# CP80_Preamp.net
KiCad netlist of a schematic drawn in Altium Designer
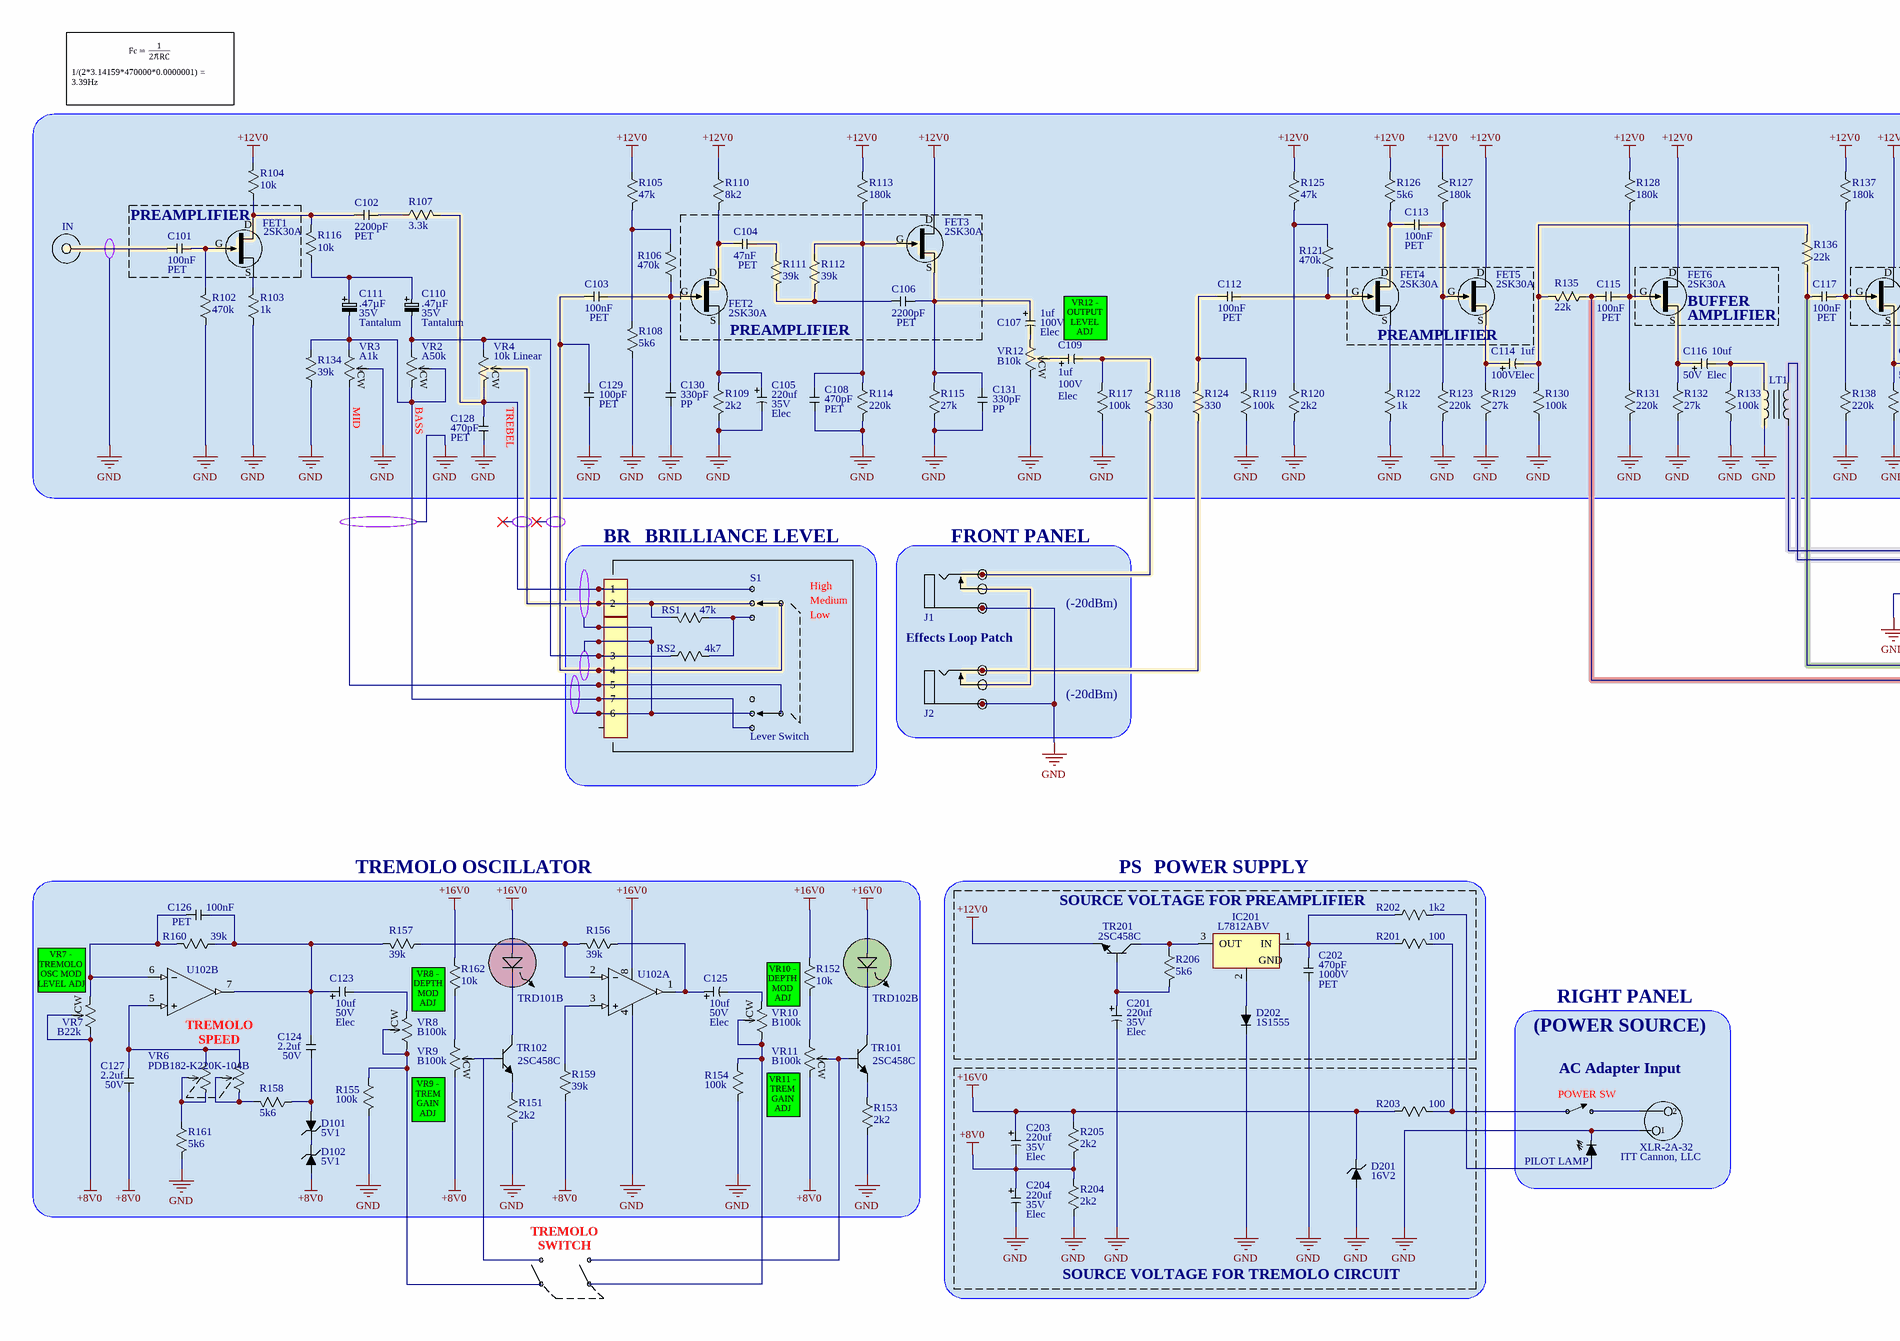
[diagram p0: CP80 Preamp.SchDoc, top left]
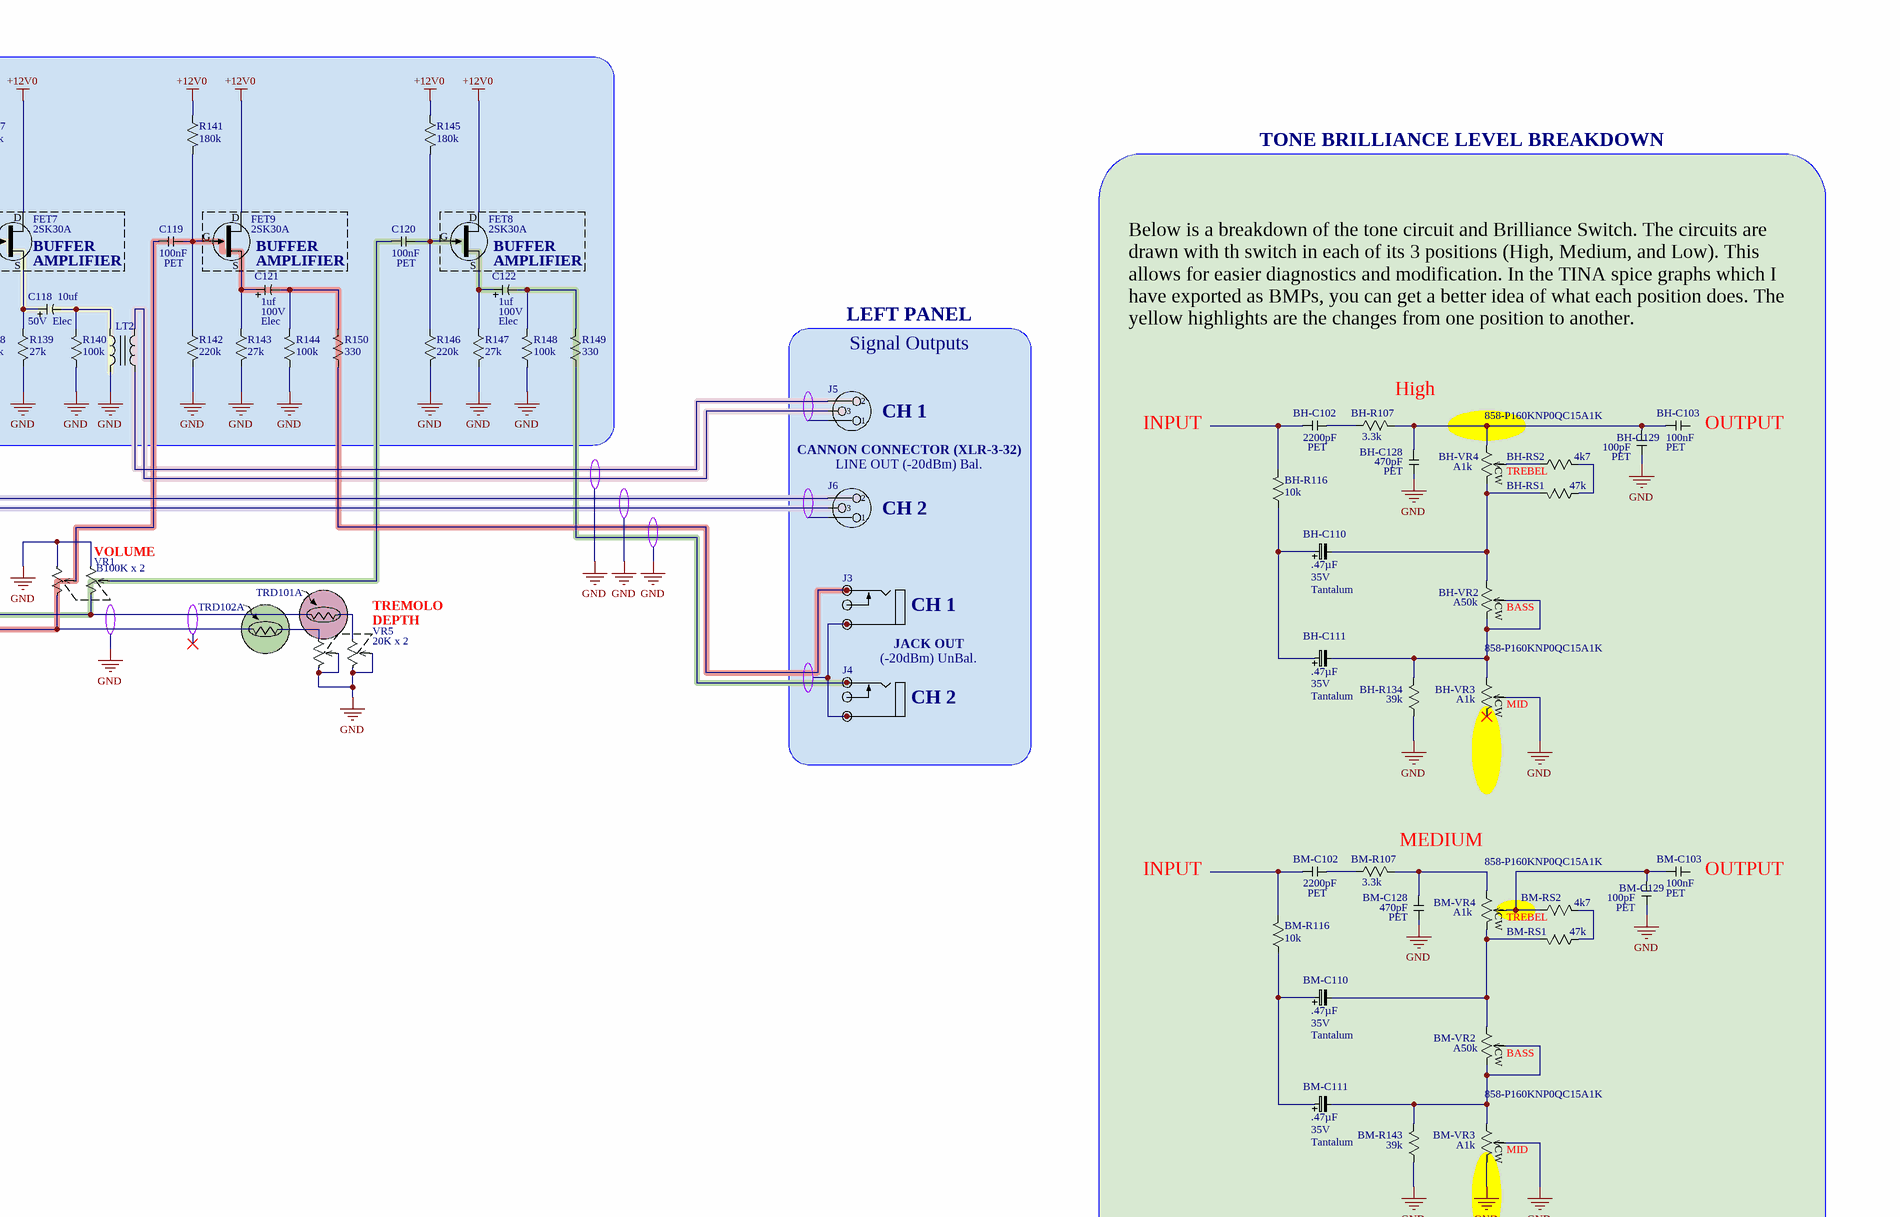
[diagram p1: CP80 Preamp.SchDoc, top right]
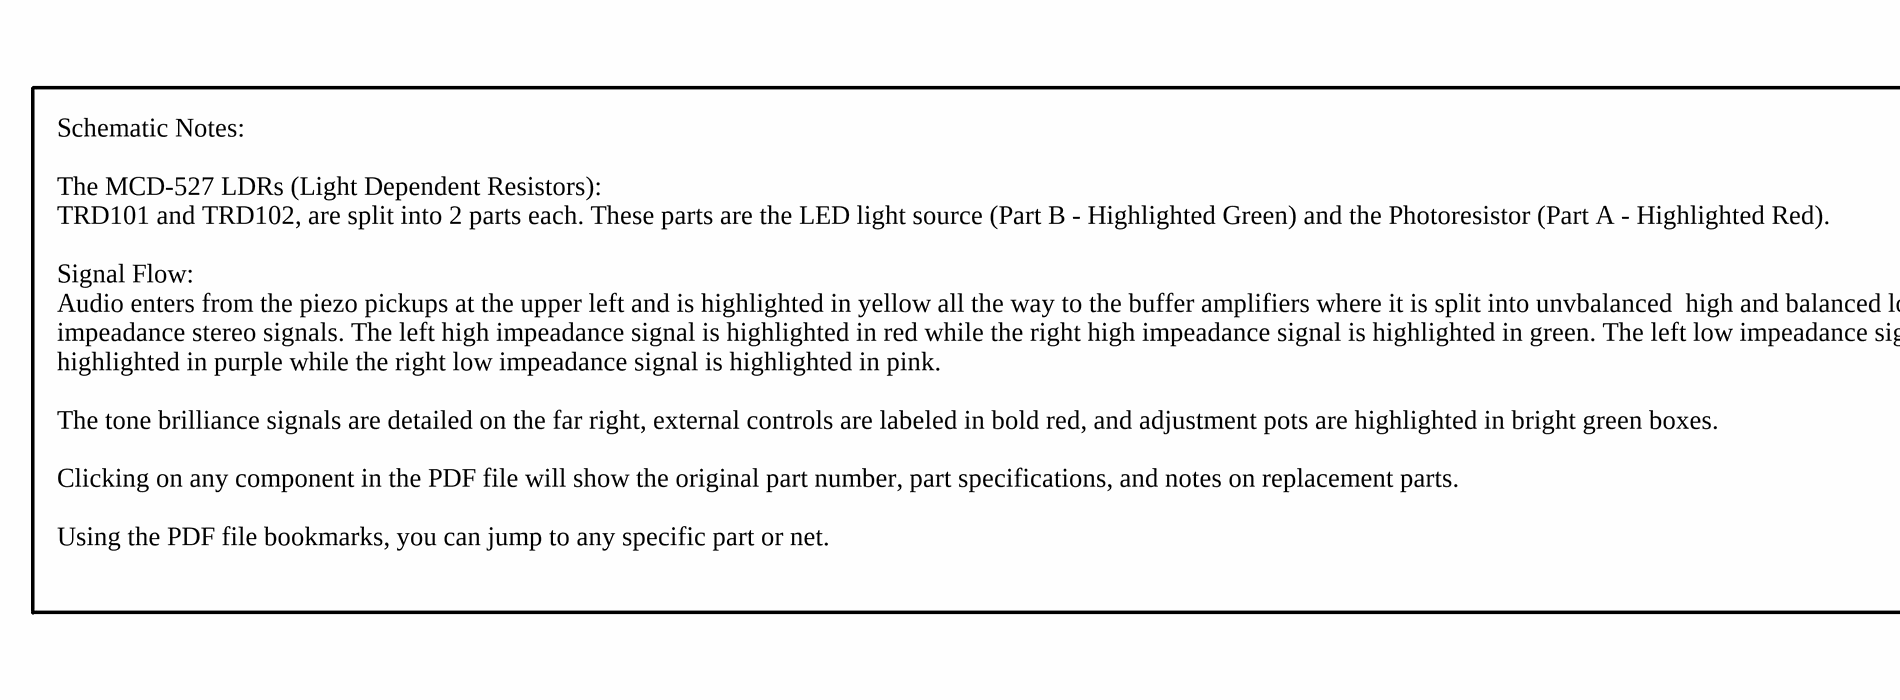
[diagram p2: CP80 Preamp.SchDoc, bottom left]
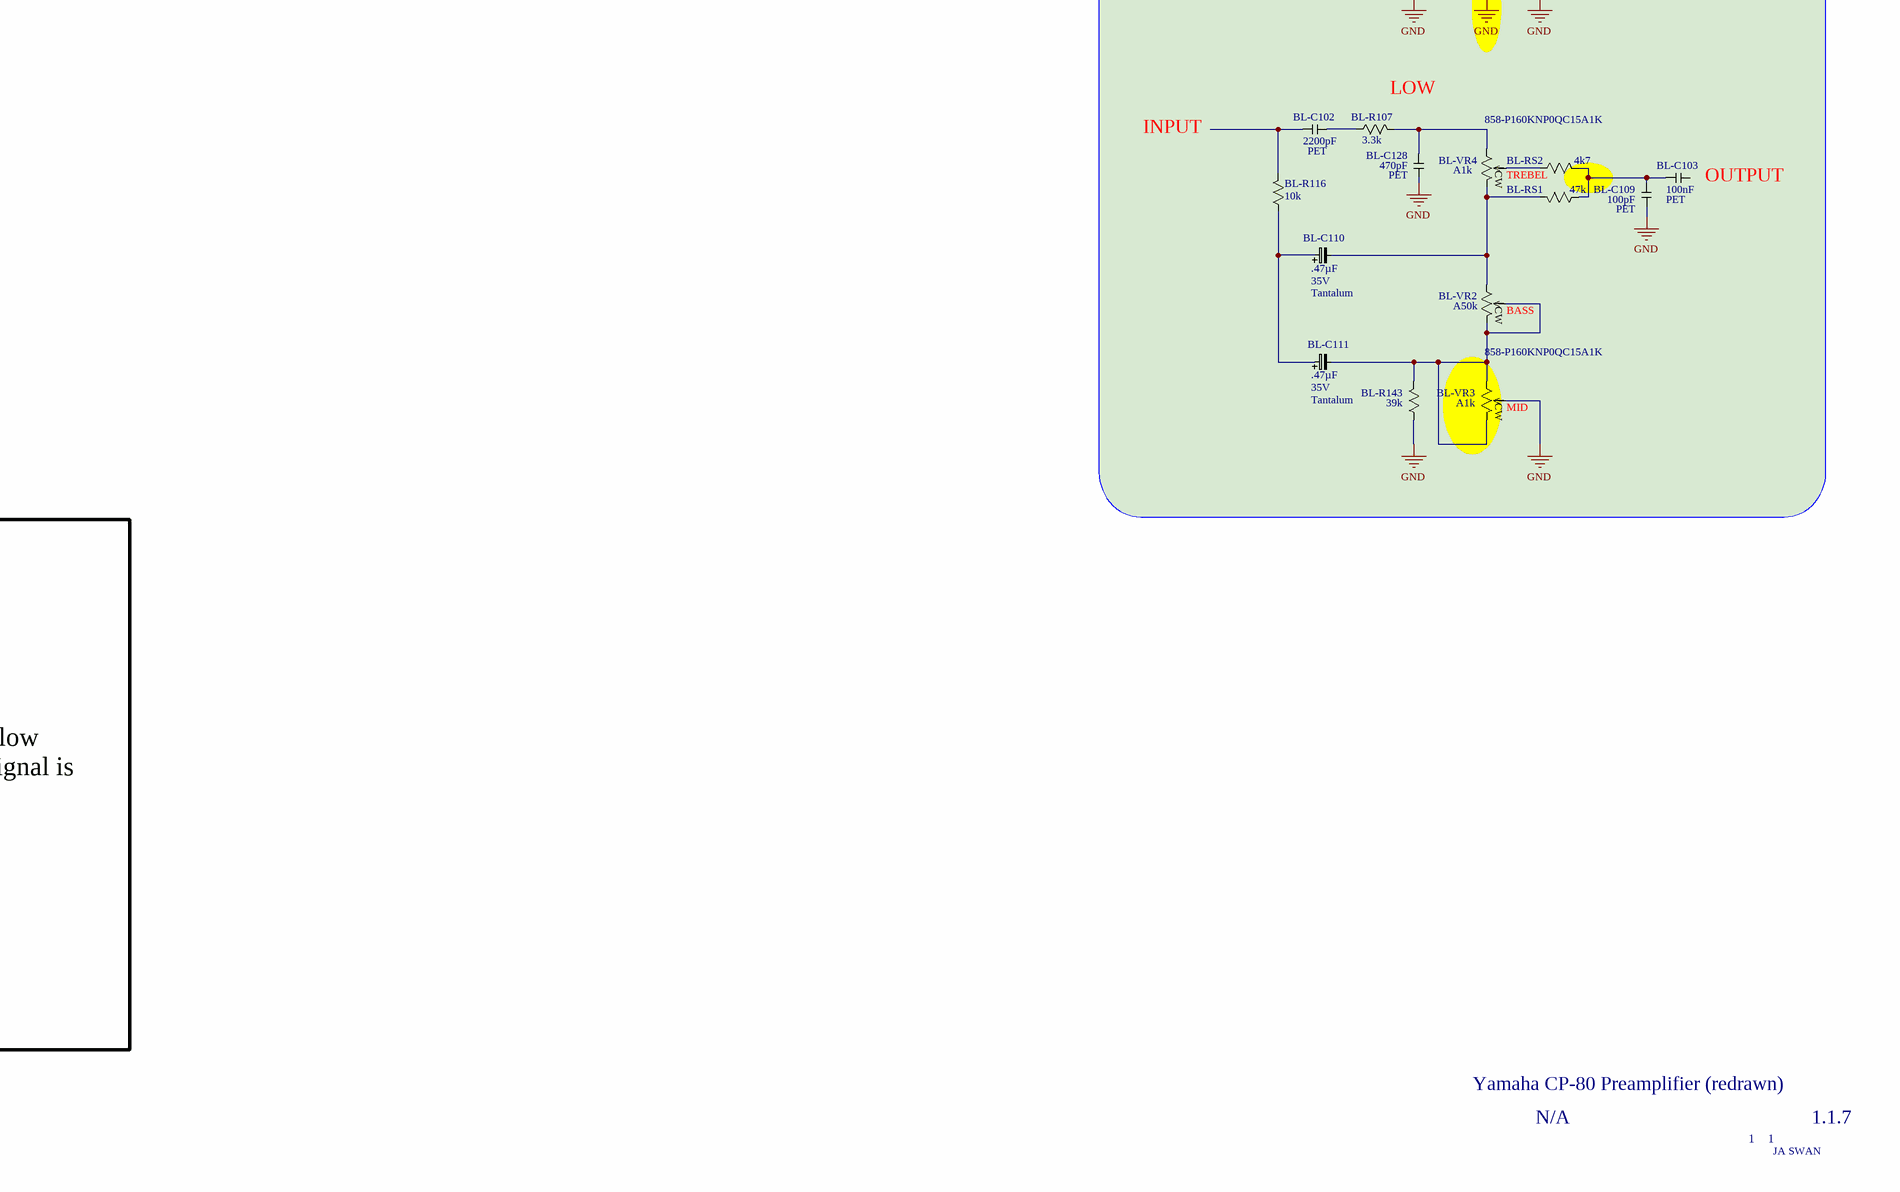
[diagram p3: CP80 Preamp.SchDoc, bottom right]

(export (version "E")
  (design (tool "Eeschema 10.0.6"))
  (components
    (comp (ref "BH-C102")
      (value "2200pF")
      (fields
        (field (name "MANUFACTURER") "KEMET")
        (field (name "CAPACITOR TYPE") "PET")
        (field (name "TOLERANCE") "5%")
        (field (name "Comment") "B32671L1222J000")
      )
      (libsource (lib "CP80 Preamp") (part "Cap_Non_Pol_2200pF"))
    )
    (comp (ref "BH-C103")
      (value "100nF")
      (fields
        (field (name "MANUFACTURER") "KEMET")
        (field (name "CAPACITOR TYPE") "PET")
        (field (name "TOLERANCE") "20%")
        (field (name "Comment") "ECW-FE2W104JA")
      )
      (libsource (lib "CP80 Preamp") (part "Cap_Non_Pol_100nF"))
    )
    (comp (ref "BH-C110")
      (value ".47µF")
      (fields
        (field (name "MANUFACTURER") "KMET")
        (field (name "TOLERANCE") "10%")
        (field (name "VOLTAGE RATING") "35V")
        (field (name "CAPACITOR TYPE") "Tantalum")
        (field (name "Comment") "T356A474K035AT")
      )
      (libsource (lib "CP80 Preamp") (part "Cap_Tant_0u47"))
    )
    (comp (ref "BH-C111")
      (value ".47µF")
      (fields
        (field (name "MANUFACTURER") "KMET")
        (field (name "TOLERANCE") "10%")
        (field (name "VOLTAGE RATING") "35V")
        (field (name "CAPACITOR TYPE") "Tantalum")
        (field (name "Comment") "T356A474K035AT")
      )
      (libsource (lib "CP80 Preamp") (part "Cap_Tant_0u47"))
    )
    (comp (ref "BH-C128")
      (value "470pF")
      (fields
        (field (name "MANUFACTURER") "KMET")
        (field (name "CAPACITOR TYPE") "PET")
        (field (name "TOLERANCE") "5%")
        (field (name "Comment") "R76QF0470DQ00J")
      )
      (libsource (lib "CP80 Preamp") (part "Cap_Non_Pol_470pF"))
    )
    (comp (ref "BH-C129")
      (value "100pF")
      (fields
        (field (name "MANUFACTURER") "KMET")
        (field (name "TOLERANCE") "5%")
        (field (name "CAPACITOR TYPE") "PET")
        (field (name "Comment") "R76UI0100SE40J")
      )
      (libsource (lib "CP80 Preamp") (part "Cap_Non_Pol_100pF"))
    )
    (comp (ref "BH-R107")
      (value "3.3k")
      (fields
        (field (name "POWER") "250mW")
        (field (name "MANUFACTURER") "Yageo")
        (field (name "TOLERANCE") "1%")
      )
      (libsource (lib "CP80 Preamp") (part "Resistor_3k3"))
    )
    (comp (ref "BH-R116")
      (value "10k")
      (fields
        (field (name "TOLERANCE") "1%")
        (field (name "POWER") "250mW")
        (field (name "MANUFACTURER") "Yageo")
      )
      (libsource (lib "CP80 Preamp") (part "Resistor_10k"))
    )
    (comp (ref "BH-R134")
      (value "39k")
      (fields
        (field (name "TOLERANCE") "1%")
        (field (name "MANUFACTURER") "Yageo")
        (field (name "POWER") "250mW")
      )
      (libsource (lib "CP80 Preamp") (part "Resistor_39k"))
    )
    (comp (ref "BH-RS1")
      (value "47k")
      (fields
        (field (name "TOLERANCE") "1%")
        (field (name "MANUFACTURER") "Yageo")
        (field (name "POWER") "250mW")
      )
      (libsource (lib "CP80 Preamp") (part "Resistor_47k"))
    )
    (comp (ref "BH-RS2")
      (value "4k7")
      (fields
        (field (name "TOLERANCE") "1%")
        (field (name "MANUFACTURER") "Yageo")
        (field (name "POWER") "250mW")
      )
      (libsource (lib "CP80 Preamp") (part "Resistor_4k7"))
    )
    (comp (ref "BH-VR2")
      (value "A50k")
      (fields
        (field (name "MANUFACTURER") "Various")
        (field (name "POWER") "200mW")
        (field (name "TOLERANCE") "20%")
      )
      (libsource (lib "CP80 Preamp") (part "Pot, Single, Cond Plastic, 50k, Log"))
    )
    (comp (ref "BH-VR3")
      (value "A1k")
      (fields
        (field (name "MANUFACTURER") "Bourns")
        (field (name "POWER") "250mW")
        (field (name "TOLERANCE") "20%")
        (field (name "SUPPLIER PART NUMBER 1") "858-P160KNP0QC15A1K")
      )
      (libsource (lib "CP80 Preamp") (part "Pot, Single, Cond Plastic, 1k, Log"))
    )
    (comp (ref "BH-VR4")
      (value "A1k")
      (fields
        (field (name "MANUFACTURER") "Bourns")
        (field (name "POWER") "250mW")
        (field (name "TOLERANCE") "20%")
        (field (name "SUPPLIER PART NUMBER 1") "858-P160KNP0QC15A1K")
      )
      (libsource (lib "CP80 Preamp") (part "Pot, Single, Cond Plastic, 1k, Log"))
    )
    (comp (ref "BL-C102")
      (value "2200pF")
      (fields
        (field (name "MANUFACTURER") "KEMET")
        (field (name "CAPACITOR TYPE") "PET")
        (field (name "TOLERANCE") "5%")
        (field (name "Comment") "B32671L1222J000")
      )
      (libsource (lib "CP80 Preamp") (part "Cap_Non_Pol_2200pF"))
    )
    (comp (ref "BL-C103")
      (value "100nF")
      (fields
        (field (name "MANUFACTURER") "KEMET")
        (field (name "CAPACITOR TYPE") "PET")
        (field (name "TOLERANCE") "20%")
        (field (name "Comment") "ECW-FE2W104JA")
      )
      (libsource (lib "CP80 Preamp") (part "Cap_Non_Pol_100nF"))
    )
    (comp (ref "BL-C109")
      (value "100pF")
      (fields
        (field (name "MANUFACTURER") "KMET")
        (field (name "TOLERANCE") "5%")
        (field (name "CAPACITOR TYPE") "PET")
        (field (name "Comment") "R76UI0100SE40J")
      )
      (libsource (lib "CP80 Preamp") (part "Cap_Non_Pol_100pF"))
    )
    (comp (ref "BL-C110")
      (value ".47µF")
      (fields
        (field (name "MANUFACTURER") "KMET")
        (field (name "TOLERANCE") "10%")
        (field (name "VOLTAGE RATING") "35V")
        (field (name "CAPACITOR TYPE") "Tantalum")
        (field (name "Comment") "T356A474K035AT")
      )
      (libsource (lib "CP80 Preamp") (part "Cap_Tant_0u47"))
    )
    (comp (ref "BL-C111")
      (value ".47µF")
      (fields
        (field (name "MANUFACTURER") "KMET")
        (field (name "TOLERANCE") "10%")
        (field (name "VOLTAGE RATING") "35V")
        (field (name "CAPACITOR TYPE") "Tantalum")
        (field (name "Comment") "T356A474K035AT")
      )
      (libsource (lib "CP80 Preamp") (part "Cap_Tant_0u47"))
    )
    (comp (ref "BL-C128")
      (value "470pF")
      (fields
        (field (name "MANUFACTURER") "KMET")
        (field (name "CAPACITOR TYPE") "PET")
        (field (name "TOLERANCE") "5%")
        (field (name "Comment") "R76QF0470DQ00J")
      )
      (libsource (lib "CP80 Preamp") (part "Cap_Non_Pol_470pF"))
    )
    (comp (ref "BL-R107")
      (value "3.3k")
      (fields
        (field (name "POWER") "250mW")
        (field (name "MANUFACTURER") "Yageo")
        (field (name "TOLERANCE") "1%")
      )
      (libsource (lib "CP80 Preamp") (part "Resistor_3k3"))
    )
    (comp (ref "BL-R116")
      (value "10k")
      (fields
        (field (name "TOLERANCE") "1%")
        (field (name "POWER") "250mW")
        (field (name "MANUFACTURER") "Yageo")
      )
      (libsource (lib "CP80 Preamp") (part "Resistor_10k"))
    )
    (comp (ref "BL-R143")
      (value "39k")
      (fields
        (field (name "TOLERANCE") "1%")
        (field (name "MANUFACTURER") "Yageo")
        (field (name "POWER") "250mW")
      )
      (libsource (lib "CP80 Preamp") (part "Resistor_39k"))
    )
    (comp (ref "BL-RS1")
      (value "47k")
      (fields
        (field (name "TOLERANCE") "1%")
        (field (name "MANUFACTURER") "Yageo")
        (field (name "POWER") "250mW")
      )
      (libsource (lib "CP80 Preamp") (part "Resistor_47k"))
    )
    (comp (ref "BL-RS2")
      (value "4k7")
      (fields
        (field (name "TOLERANCE") "1%")
        (field (name "MANUFACTURER") "Yageo")
        (field (name "POWER") "250mW")
      )
      (libsource (lib "CP80 Preamp") (part "Resistor_4k7"))
    )
    (comp (ref "BL-VR2")
      (value "A50k")
      (fields
        (field (name "MANUFACTURER") "Various")
        (field (name "POWER") "200mW")
        (field (name "TOLERANCE") "20%")
      )
      (libsource (lib "CP80 Preamp") (part "Pot, Single, Cond Plastic, 50k, Log"))
    )
    (comp (ref "BL-VR3")
      (value "A1k")
      (fields
        (field (name "MANUFACTURER") "Bourns")
        (field (name "POWER") "250mW")
        (field (name "TOLERANCE") "20%")
        (field (name "SUPPLIER PART NUMBER 1") "858-P160KNP0QC15A1K")
      )
      (libsource (lib "CP80 Preamp") (part "Pot, Single, Cond Plastic, 1k, Log"))
    )
    (comp (ref "BL-VR4")
      (value "A1k")
      (fields
        (field (name "MANUFACTURER") "Bourns")
        (field (name "POWER") "250mW")
        (field (name "TOLERANCE") "20%")
        (field (name "SUPPLIER PART NUMBER 1") "858-P160KNP0QC15A1K")
      )
      (libsource (lib "CP80 Preamp") (part "Pot, Single, Cond Plastic, 1k, Log"))
    )
    (comp (ref "BM-C102")
      (value "2200pF")
      (fields
        (field (name "MANUFACTURER") "KEMET")
        (field (name "CAPACITOR TYPE") "PET")
        (field (name "TOLERANCE") "5%")
        (field (name "Comment") "B32671L1222J000")
      )
      (libsource (lib "CP80 Preamp") (part "Cap_Non_Pol_2200pF"))
    )
    (comp (ref "BM-C103")
      (value "100nF")
      (fields
        (field (name "MANUFACTURER") "KEMET")
        (field (name "CAPACITOR TYPE") "PET")
        (field (name "TOLERANCE") "20%")
        (field (name "Comment") "ECW-FE2W104JA")
      )
      (libsource (lib "CP80 Preamp") (part "Cap_Non_Pol_100nF"))
    )
    (comp (ref "BM-C110")
      (value ".47µF")
      (fields
        (field (name "MANUFACTURER") "KMET")
        (field (name "TOLERANCE") "10%")
        (field (name "VOLTAGE RATING") "35V")
        (field (name "CAPACITOR TYPE") "Tantalum")
        (field (name "Comment") "T356A474K035AT")
      )
      (libsource (lib "CP80 Preamp") (part "Cap_Tant_0u47"))
    )
    (comp (ref "BM-C111")
      (value ".47µF")
      (fields
        (field (name "MANUFACTURER") "KMET")
        (field (name "TOLERANCE") "10%")
        (field (name "VOLTAGE RATING") "35V")
        (field (name "CAPACITOR TYPE") "Tantalum")
        (field (name "Comment") "T356A474K035AT")
      )
      (libsource (lib "CP80 Preamp") (part "Cap_Tant_0u47"))
    )
    (comp (ref "BM-C128")
      (value "470pF")
      (fields
        (field (name "MANUFACTURER") "KMET")
        (field (name "CAPACITOR TYPE") "PET")
        (field (name "TOLERANCE") "5%")
        (field (name "Comment") "R76QF0470DQ00J")
      )
      (libsource (lib "CP80 Preamp") (part "Cap_Non_Pol_470pF"))
    )
    (comp (ref "BM-C129")
      (value "100pF")
      (fields
        (field (name "MANUFACTURER") "KMET")
        (field (name "TOLERANCE") "5%")
        (field (name "CAPACITOR TYPE") "PET")
        (field (name "Comment") "R76UI0100SE40J")
      )
      (libsource (lib "CP80 Preamp") (part "Cap_Non_Pol_100pF"))
    )
    (comp (ref "BM-R107")
      (value "3.3k")
      (fields
        (field (name "POWER") "250mW")
        (field (name "MANUFACTURER") "Yageo")
        (field (name "TOLERANCE") "1%")
      )
      (libsource (lib "CP80 Preamp") (part "Resistor_3k3"))
    )
    (comp (ref "BM-R116")
      (value "10k")
      (fields
        (field (name "TOLERANCE") "1%")
        (field (name "POWER") "250mW")
        (field (name "MANUFACTURER") "Yageo")
      )
      (libsource (lib "CP80 Preamp") (part "Resistor_10k"))
    )
    (comp (ref "BM-R143")
      (value "39k")
      (fields
        (field (name "TOLERANCE") "1%")
        (field (name "MANUFACTURER") "Yageo")
        (field (name "POWER") "250mW")
      )
      (libsource (lib "CP80 Preamp") (part "Resistor_39k"))
    )
    (comp (ref "BM-RS1")
      (value "47k")
      (fields
        (field (name "TOLERANCE") "1%")
        (field (name "MANUFACTURER") "Yageo")
        (field (name "POWER") "250mW")
      )
      (libsource (lib "CP80 Preamp") (part "Resistor_47k"))
    )
    (comp (ref "BM-RS2")
      (value "4k7")
      (fields
        (field (name "TOLERANCE") "1%")
        (field (name "MANUFACTURER") "Yageo")
        (field (name "POWER") "250mW")
      )
      (libsource (lib "CP80 Preamp") (part "Resistor_4k7"))
    )
    (comp (ref "BM-VR2")
      (value "A50k")
      (fields
        (field (name "MANUFACTURER") "Various")
        (field (name "POWER") "200mW")
        (field (name "TOLERANCE") "20%")
      )
      (libsource (lib "CP80 Preamp") (part "Pot, Single, Cond Plastic, 50k, Log"))
    )
    (comp (ref "BM-VR3")
      (value "A1k")
      (fields
        (field (name "MANUFACTURER") "Bourns")
        (field (name "POWER") "250mW")
        (field (name "TOLERANCE") "20%")
        (field (name "SUPPLIER PART NUMBER 1") "858-P160KNP0QC15A1K")
      )
      (libsource (lib "CP80 Preamp") (part "Pot, Single, Cond Plastic, 1k, Log"))
    )
    (comp (ref "BM-VR4")
      (value "A1k")
      (fields
        (field (name "MANUFACTURER") "Bourns")
        (field (name "POWER") "250mW")
        (field (name "TOLERANCE") "20%")
        (field (name "SUPPLIER PART NUMBER 1") "858-P160KNP0QC15A1K")
      )
      (libsource (lib "CP80 Preamp") (part "Pot, Single, Cond Plastic, 1k, Log"))
    )
    (comp (ref "C101")
      (value "100nF")
      (fields
        (field (name "MANUFACTURER") "KEMET")
        (field (name "CAPACITOR TYPE") "PET")
        (field (name "TOLERANCE") "20%")
        (field (name "Comment") "ECW-FE2W104JA")
      )
      (libsource (lib "CP80 Preamp") (part "Cap_Non_Pol_100nF"))
    )
    (comp (ref "C102")
      (value "2200pF")
      (fields
        (field (name "MANUFACTURER") "KEMET")
        (field (name "CAPACITOR TYPE") "PET")
        (field (name "TOLERANCE") "5%")
        (field (name "Comment") "B32671L1222J000")
      )
      (libsource (lib "CP80 Preamp") (part "Cap_Non_Pol_2200pF"))
    )
    (comp (ref "C103")
      (value "100nF")
      (fields
        (field (name "MANUFACTURER") "KEMET")
        (field (name "CAPACITOR TYPE") "PET")
        (field (name "TOLERANCE") "20%")
        (field (name "Comment") "ECW-FE2W104JA")
      )
      (libsource (lib "CP80 Preamp") (part "Cap_Non_Pol_100nF"))
    )
    (comp (ref "C104")
      (value "47nF")
      (fields
        (field (name "MANUFACTURER") "Various")
        (field (name "CAPACITOR TYPE") "PET")
        (field (name "TOLERANCE") "5%")
        (field (name "Comment") "R76MF24705050J")
      )
      (libsource (lib "CP80 Preamp") (part "Cap_Non_Pol_47nF"))
    )
    (comp (ref "C105")
      (value "220uf")
      (fields
        (field (name "MANUFACTURER") "Generic")
        (field (name "TOLERANCE") "20%")
        (field (name "VOLTAGE RATING") "35V")
        (field (name "CAPACITOR TYPE") "Elec")
        (field (name "Comment") "UKT1V221MPD")
      )
      (libsource (lib "CP80 Preamp") (part "Cap_Pol_220uF_35V"))
    )
    (comp (ref "C106")
      (value "2200pF")
      (fields
        (field (name "MANUFACTURER") "KEMET")
        (field (name "CAPACITOR TYPE") "PET")
        (field (name "TOLERANCE") "5%")
        (field (name "Comment") "B32671L1222J000")
      )
      (libsource (lib "CP80 Preamp") (part "Cap_Non_Pol_2200pF"))
    )
    (comp (ref "C107")
      (value "1uf")
      (fields
        (field (name "MANUFACTURER") "Generic")
        (field (name "TOLERANCE") "20%")
        (field (name "VOLTAGE RATING") "100V")
        (field (name "CAPACITOR TYPE") "Elec")
        (field (name "Comment") "105BPS100M")
      )
      (libsource (lib "CP80 Preamp") (part "Cap_Pol_Elec_1u0_50V"))
    )
    (comp (ref "C108")
      (value "470pF")
      (fields
        (field (name "MANUFACTURER") "KMET")
        (field (name "CAPACITOR TYPE") "PET")
        (field (name "TOLERANCE") "5%")
        (field (name "Comment") "R76QF0470DQ00J")
      )
      (libsource (lib "CP80 Preamp") (part "Cap_Non_Pol_470pF"))
    )
    (comp (ref "C109")
      (value "1uf")
      (fields
        (field (name "MANUFACTURER") "Generic")
        (field (name "TOLERANCE") "20%")
        (field (name "VOLTAGE RATING") "100V")
        (field (name "CAPACITOR TYPE") "Elec")
        (field (name "Comment") "105BPS100M")
      )
      (libsource (lib "CP80 Preamp") (part "Cap_Pol_Elec_1u0_50V"))
    )
    (comp (ref "C110")
      (value ".47µF")
      (fields
        (field (name "MANUFACTURER") "KMET")
        (field (name "TOLERANCE") "10%")
        (field (name "VOLTAGE RATING") "35V")
        (field (name "CAPACITOR TYPE") "Tantalum")
        (field (name "Comment") "T356A474K035AT")
      )
      (libsource (lib "") (part "Cap_Tant_0u47_1"))
    )
    (comp (ref "C111")
      (value ".47µF")
      (fields
        (field (name "MANUFACTURER") "KMET")
        (field (name "TOLERANCE") "10%")
        (field (name "VOLTAGE RATING") "35V")
        (field (name "CAPACITOR TYPE") "Tantalum")
        (field (name "Comment") "T356A474K035AT")
      )
      (libsource (lib "") (part "Cap_Tant_0u47_1"))
    )
    (comp (ref "C112")
      (value "100nF")
      (fields
        (field (name "MANUFACTURER") "KEMET")
        (field (name "TOLERANCE") "20%")
        (field (name "CAPACITOR TYPE") "PET")
        (field (name "Comment") "ECW-FE2W104JA")
      )
      (libsource (lib "CP80 Preamp") (part "Cap_Non_Pol_100nF"))
    )
    (comp (ref "C113")
      (value "100nF")
      (fields
        (field (name "MANUFACTURER") "KEMET")
        (field (name "TOLERANCE") "20%")
        (field (name "CAPACITOR TYPE") "PET")
        (field (name "Comment") "ECW-FE2W104JA")
      )
      (libsource (lib "CP80 Preamp") (part "Cap_Non_Pol_100nF"))
    )
    (comp (ref "C114")
      (value "1uf")
      (fields
        (field (name "MANUFACTURER") "Generic")
        (field (name "TOLERANCE") "20%")
        (field (name "VOLTAGE RATING") "100V")
        (field (name "CAPACITOR TYPE") "Elec")
        (field (name "Comment") "105BPS100M")
      )
      (libsource (lib "CP80 Preamp") (part "Cap_Pol_Elec_1u0_50V"))
    )
    (comp (ref "C115")
      (value "100nF")
      (fields
        (field (name "MANUFACTURER") "KEMET")
        (field (name "TOLERANCE") "20%")
        (field (name "CAPACITOR TYPE") "PET")
        (field (name "Comment") "ECW-FE2W104JA")
      )
      (libsource (lib "CP80 Preamp") (part "Cap_Non_Pol_100nF"))
    )
    (comp (ref "C116")
      (value "10uf")
      (fields
        (field (name "MANUFACTURER") "Generic")
        (field (name "TOLERANCE") "20%")
        (field (name "VOLTAGE RATING") "50V")
        (field (name "CAPACITOR TYPE") "Elec")
        (field (name "Comment") "UES1H100MPM")
      )
      (libsource (lib "CP80 Preamp") (part "Cap_Pol_10u_50V"))
    )
    (comp (ref "C117")
      (value "100nF")
      (fields
        (field (name "MANUFACTURER") "KEMET")
        (field (name "TOLERANCE") "20%")
        (field (name "CAPACITOR TYPE") "PET")
        (field (name "Comment") "ECW-FE2W104JA")
      )
      (libsource (lib "CP80 Preamp") (part "Cap_Non_Pol_100nF"))
    )
    (comp (ref "C118")
      (value "10uf")
      (fields
        (field (name "MANUFACTURER") "Generic")
        (field (name "TOLERANCE") "20%")
        (field (name "VOLTAGE RATING") "50V")
        (field (name "CAPACITOR TYPE") "Elec")
        (field (name "Comment") "UES1H100MPM")
      )
      (libsource (lib "CP80 Preamp") (part "Cap_Pol_10u_50V"))
    )
    (comp (ref "C119")
      (value "100nF")
      (fields
        (field (name "MANUFACTURER") "KEMET")
        (field (name "TOLERANCE") "20%")
        (field (name "CAPACITOR TYPE") "PET")
        (field (name "Comment") "ECW-FE2W104JA")
      )
      (libsource (lib "CP80 Preamp") (part "Cap_Non_Pol_100nF"))
    )
    (comp (ref "C120")
      (value "100nF")
      (fields
        (field (name "MANUFACTURER") "KEMET")
        (field (name "TOLERANCE") "20%")
        (field (name "CAPACITOR TYPE") "PET")
        (field (name "Comment") "ECW-FE2W104JA")
      )
      (libsource (lib "CP80 Preamp") (part "Cap_Non_Pol_100nF"))
    )
    (comp (ref "C121")
      (value "1uf")
      (fields
        (field (name "MANUFACTURER") "Generic")
        (field (name "TOLERANCE") "20%")
        (field (name "VOLTAGE RATING") "100V")
        (field (name "CAPACITOR TYPE") "Elec")
        (field (name "Comment") "105BPS100M")
      )
      (libsource (lib "CP80 Preamp") (part "Cap_Pol_Elec_1u0_50V"))
    )
    (comp (ref "C122")
      (value "1uf")
      (fields
        (field (name "MANUFACTURER") "Generic")
        (field (name "TOLERANCE") "20%")
        (field (name "VOLTAGE RATING") "100V")
        (field (name "CAPACITOR TYPE") "Elec")
        (field (name "Comment") "105BPS100M")
      )
      (libsource (lib "CP80 Preamp") (part "Cap_Pol_Elec_1u0_50V"))
    )
    (comp (ref "C123")
      (value "10uf")
      (fields
        (field (name "MANUFACTURER") "Generic")
        (field (name "TOLERANCE") "20%")
        (field (name "VOLTAGE RATING") "50V")
        (field (name "CAPACITOR TYPE") "Elec")
        (field (name "Comment") "UES1H100MPM")
      )
      (libsource (lib "CP80 Preamp") (part "Cap_Pol_10u_50V"))
    )
    (comp (ref "C124")
      (value "2.2uf")
      (fields
        (field (name "VOLTAGE RATING") "50V")
        (field (name "MANUFACTURER") "Generic")
        (field (name "TOLERANCE") "20%")
        (field (name "Comment") "225BPS050M")
      )
      (libsource (lib "CP80 Preamp") (part "Cap_Non_Pol_2u2_50V"))
    )
    (comp (ref "C125")
      (value "10uf")
      (fields
        (field (name "MANUFACTURER") "Generic")
        (field (name "TOLERANCE") "20%")
        (field (name "VOLTAGE RATING") "50V")
        (field (name "CAPACITOR TYPE") "Elec")
        (field (name "Comment") "UES1H100MPM")
      )
      (libsource (lib "CP80 Preamp") (part "Cap_Pol_10u_50V"))
    )
    (comp (ref "C126")
      (value "100nF")
      (fields
        (field (name "MANUFACTURER") "KEMET")
        (field (name "TOLERANCE") "20%")
        (field (name "CAPACITOR TYPE") "PET")
        (field (name "Comment") "ECW-FE2W104JA")
      )
      (libsource (lib "CP80 Preamp") (part "Cap_Non_Pol_100nF"))
    )
    (comp (ref "C127")
      (value "2.2uf")
      (fields
        (field (name "VOLTAGE RATING") "50V")
        (field (name "MANUFACTURER") "Generic")
        (field (name "TOLERANCE") "20%")
        (field (name "Comment") "225BPS050M")
      )
      (libsource (lib "CP80 Preamp") (part "Cap_Non_Pol_2u2_50V"))
    )
    (comp (ref "C128")
      (value "470pF")
      (fields
        (field (name "MANUFACTURER") "KMET")
        (field (name "CAPACITOR TYPE") "PET")
        (field (name "TOLERANCE") "5%")
        (field (name "Comment") "R76QF0470DQ00J")
      )
      (libsource (lib "CP80 Preamp") (part "Cap_Non_Pol_470pF"))
    )
    (comp (ref "C129")
      (value "100pF")
      (fields
        (field (name "MANUFACTURER") "KMET")
        (field (name "CAPACITOR TYPE") "PET")
        (field (name "TOLERANCE") "5%")
        (field (name "Comment") "R76UI0100SE40J")
      )
      (libsource (lib "CP80 Preamp") (part "Cap_Non_Pol_100pF"))
    )
    (comp (ref "C130")
      (value "330pF")
      (fields
        (field (name "MANUFACTURER") "Various")
        (field (name "CAPACITOR TYPE") "PP")
        (field (name "TOLERANCE") "5%")
        (field (name "Comment") "PFR5331J630J11L4BULK")
      )
      (libsource (lib "CP80 Preamp") (part "Cap_Non_Pol_330pF"))
    )
    (comp (ref "C131")
      (value "330pF")
      (fields
        (field (name "MANUFACTURER") "Various")
        (field (name "CAPACITOR TYPE") "PP")
        (field (name "TOLERANCE") "5%")
        (field (name "Comment") "PFR5331J630J11L4BULK")
      )
      (libsource (lib "CP80 Preamp") (part "Cap_Non_Pol_330pF"))
    )
    (comp (ref "C201")
      (value "220uf")
      (fields
        (field (name "MANUFACTURER") "Generic")
        (field (name "TOLERANCE") "20%")
        (field (name "VOLTAGE RATING") "35V")
        (field (name "CAPACITOR TYPE") "Elec")
        (field (name "Comment") "UKT1V221MPD")
      )
      (libsource (lib "CP80 Preamp") (part "Cap_Pol_220uF_35V"))
    )
    (comp (ref "C202")
      (value "470pF")
      (fields
        (field (name "MANUFACTURER") "KMET")
        (field (name "TOLERANCE") "5%")
        (field (name "VOLTAGE RATING") "1000V")
        (field (name "CAPACITOR TYPE") "PET")
        (field (name "Comment") "R76QF0470DQ00J")
      )
      (libsource (lib "CP80 Preamp") (part "Cap_Non_Pol_470pF"))
    )
    (comp (ref "C203")
      (value "220uf")
      (fields
        (field (name "MANUFACTURER") "Generic")
        (field (name "TOLERANCE") "20%")
        (field (name "VOLTAGE RATING") "35V")
        (field (name "CAPACITOR TYPE") "Elec")
        (field (name "Comment") "UKT1V221MPD")
      )
      (libsource (lib "CP80 Preamp") (part "Cap_Pol_220uF_35V"))
    )
    (comp (ref "C204")
      (value "220uf")
      (fields
        (field (name "MANUFACTURER") "Generic")
        (field (name "TOLERANCE") "20%")
        (field (name "VOLTAGE RATING") "35V")
        (field (name "CAPACITOR TYPE") "Elec")
        (field (name "Comment") "UKT1V221MPD")
      )
      (libsource (lib "CP80 Preamp") (part "Cap_Pol_220uF_35V"))
    )
    (comp (ref "D1")
      (value "WP7113ID")
      (footprint "LED_SMD_0805")
      (fields (field (name "MANUFACTURER") "Various") (field (name "FUNCTION") "PILOT LAMP"))
      (libsource (lib "CP80 Preamp") (part "LED, Red, 5mm"))
    )
    (comp (ref "D101")
      (value "1N5231BTR")
      (footprint "SODFL250X100-2N")
      (description "Zener Diode 5.1 V 500 mW 5%\r\n\r\nIf replacing, any 5V1 zener capable of 500mW is fine")
      (fields
        (field (name "TOLERANCE") "5%")
        (field (name "VOLTAGE - ZENER (NOM)") "5V1")
        (field (name "MANUFACTURER") "Japan Radio Co LTD")
      )
      (libsource (lib "CP80 Preamp") (part "Diode, Zener, 5V1, 500mW"))
    )
    (comp (ref "D102")
      (value "1N5231BTR")
      (footprint "SODFL250X100-2N")
      (description "Zener Diode 5.1 V 500 mW 5%\r\n\r\nIf replacing, any 5V1 zener capable of 500mW is fine")
      (fields
        (field (name "TOLERANCE") "5%")
        (field (name "VOLTAGE - ZENER (NOM)") "5V1")
        (field (name "MANUFACTURER") "Japan Radio Co LTD")
      )
      (libsource (lib "CP80 Preamp") (part "Diode, Zener, 5V1, 500mW"))
    )
    (comp (ref "D201")
      (value "1N5246B")
      (footprint "SODFL250X100-2N")
      (description "Zener Diode 16V2 500 mW 5%\r\n\r\nIf replacing, any 16V2 zener with 500mW capability will work.")
      (fields
        (field (name "TOLERANCE") "5%")
        (field (name "VOLTAGE - ZENER (NOM)") "16V2")
        (field (name "MANUFACTURER") "Japan Radio Co LTD")
      )
      (libsource (lib "CP80 Preamp") (part "Diode, Zener, 16V2, 500mW"))
    )
    (comp (ref "D202")
      (value "1N4148")
      (fields (field (name "MANUFACTURER") "Toshiba") (field (name "PART NUMBER") "1S1555"))
      (libsource (lib "CP80 Preamp") (part "Diode, Gen Purpose"))
    )
    (comp (ref "FET1")
      (value "Transistor, JFET, N Ch, TO-92")
      (footprint "TO92")
      (fields (field (name "MANUFACTURER") "TOSHIBA") (field (name "PART NUMBER") "2SK30A"))
      (libsource (lib "CP80 Preamp") (part "Transistor, JFET, N Ch, TO-92"))
    )
    (comp (ref "FET2")
      (value "Transistor, JFET, N Ch, TO-92")
      (footprint "TO92")
      (fields (field (name "MANUFACTURER") "TOSHIBA") (field (name "PART NUMBER") "2SK30A"))
      (libsource (lib "CP80 Preamp") (part "Transistor, JFET, N Ch, TO-92"))
    )
    (comp (ref "FET3")
      (value "Transistor, JFET, N Ch, TO-92")
      (footprint "TO92")
      (fields (field (name "MANUFACTURER") "TOSHIBA") (field (name "PART NUMBER") "2SK30A"))
      (libsource (lib "CP80 Preamp") (part "Transistor, JFET, N Ch, TO-92"))
    )
    (comp (ref "FET4")
      (value "Transistor, JFET, N Ch, TO-92")
      (footprint "TO92")
      (fields (field (name "MANUFACTURER") "TOSHIBA") (field (name "PART NUMBER") "2SK30A"))
      (libsource (lib "CP80 Preamp") (part "Transistor, JFET, N Ch, TO-92"))
    )
    (comp (ref "FET5")
      (value "Transistor, JFET, N Ch, TO-92")
      (footprint "TO92")
      (fields (field (name "MANUFACTURER") "TOSHIBA") (field (name "PART NUMBER") "2SK30A"))
      (libsource (lib "CP80 Preamp") (part "Transistor, JFET, N Ch, TO-92"))
    )
    (comp (ref "FET6")
      (value "Transistor, JFET, N Ch, TO-92")
      (footprint "TO92")
      (fields (field (name "MANUFACTURER") "TOSHIBA") (field (name "PART NUMBER") "2SK30A"))
      (libsource (lib "CP80 Preamp") (part "Transistor, JFET, N Ch, TO-92"))
    )
    (comp (ref "FET7")
      (value "Transistor, JFET, N Ch, TO-92")
      (footprint "TO92")
      (fields (field (name "MANUFACTURER") "TOSHIBA") (field (name "PART NUMBER") "2SK30A"))
      (libsource (lib "CP80 Preamp") (part "Transistor, JFET, N Ch, TO-92"))
    )
    (comp (ref "FET8")
      (value "Transistor, JFET, N Ch, TO-92")
      (footprint "TO92")
      (fields (field (name "MANUFACTURER") "TOSHIBA") (field (name "PART NUMBER") "2SK30A"))
      (libsource (lib "CP80 Preamp") (part "Transistor, JFET, N Ch, TO-92"))
    )
    (comp (ref "FET9")
      (value "Transistor, JFET, N Ch, TO-92")
      (footprint "TO92")
      (fields (field (name "MANUFACTURER") "TOSHIBA") (field (name "PART NUMBER") "2SK30A"))
      (libsource (lib "CP80 Preamp") (part "Transistor, JFET, N Ch, TO-92"))
    )
    (comp (ref "IC201")
      (value "L7812ABV")
      (footprint "TO220")
      (fields (field (name "PART NUMBER") "L7812ABV") (field (name "MANUFACTURER") "STMicroelectronics"))
      (libsource (lib "CP80 Preamp") (part "IC, REG, LINEAR, 12V, 1.5A, TO220"))
    )
    (comp (ref "IN")
      (value "Soldered Wire - Round Pad")
      (footprint "12AWG Soldered Wire - Round")
      (description "Single connection for a wire using a round pad that allows for insertion from either side")
      (fields (field (name "MANUFACTURER") "NA"))
      (libsource (lib "CP80 Preamp") (part "Soldered Wire - Round"))
    )
    (comp (ref "J1") (value "112AX") (libsource (lib "CP80 Preamp") (part "Jack, Phone, 2 Pos, Break SW")))
    (comp (ref "J2") (value "112AX") (libsource (lib "CP80 Preamp") (part "Jack, Phone, 2 Pos, Break SW")))
    (comp (ref "J3") (value "112AX") (libsource (lib "CP80 Preamp") (part "Jack, Phone, 2 Pos, Break SW")))
    (comp (ref "J4") (value "112AX") (libsource (lib "CP80 Preamp") (part "Jack, Phone, 2 Pos, Break SW")))
    (comp (ref "J5")
      (value "XLR-3-32")
      (fields (field (name "MANUFACTURER") "ITT Cannon, LLC"))
      (libsource (lib "CP80 Preamp") (part "Connector, XLR, 3 POS, Male Pins, Solder Cup"))
    )
    (comp (ref "J6")
      (value "XLR-3-32")
      (fields (field (name "MANUFACTURER") "ITT Cannon, LLC"))
      (libsource (lib "CP80 Preamp") (part "Connector, XLR, 3 POS, Male Pins, Solder Cup"))
    )
    (comp (ref "J7")
      (value "HDR2x1")
      (footprint "HDR1X2")
      (description "2 pin 0.1\" spacing header")
      (libsource (lib "CP80 Preamp") (part "HDR2x1"))
    )
    (comp (ref "J8")
      (value "HRD8x1")
      (footprint "HDR1X8")
      (description "8 pin 0.1\" header")
      (fields (field (name "MANUFACTURER") "Generic"))
      (libsource (lib "CP80 Preamp") (part "HDR8x1"))
    )
    (comp (ref "J201")
      (value "XLR-2A-32")
      (footprint "SODFL370X135-2N")
      (fields (field (name "PART NUMBER") "XLR-2A-32") (field (name "MANUFACTURER") "ITT Cannon, LLC"))
      (libsource (lib "CP80 Preamp") (part "Connector, XLR, 2 POS, Male Pins"))
    )
    (comp (ref "LT1")
      (value "GD90025")
      (footprint "SODFL370X135-2N")
      (fields (field (name "MANUFACTURER") "Diodes Incorporated"))
      (libsource (lib "CP80 Preamp") (part "Transformer, Audio Matching"))
    )
    (comp (ref "LT2")
      (value "GD90025")
      (footprint "SODFL370X135-2N")
      (fields (field (name "MANUFACTURER") "Diodes Incorporated"))
      (libsource (lib "CP80 Preamp") (part "Transformer, Audio Matching"))
    )
    (comp (ref "PS1")
      (value "POWER SW")
      (description "Slide switch. Need to find replacement part number")
      (libsource (lib "CP80 Preamp") (part "Switch, Toggle, SPST"))
    )
    (comp (ref "R102")
      (value "470k")
      (fields
        (field (name "MANUFACTURER") "Yageo")
        (field (name "POWER") "250mW")
        (field (name "TOLERANCE") "1%")
      )
      (libsource (lib "CP80 Preamp") (part "Resistor_470k"))
    )
    (comp (ref "R103")
      (value "1k")
      (fields
        (field (name "TOLERANCE") "1%")
        (field (name "MANUFACTURER") "Yageo")
        (field (name "POWER") "250mW")
      )
      (libsource (lib "CP80 Preamp") (part "Resistor_1k"))
    )
    (comp (ref "R104")
      (value "10k")
      (fields
        (field (name "TOLERANCE") "1%")
        (field (name "POWER") "250mW")
        (field (name "MANUFACTURER") "Yageo")
      )
      (libsource (lib "CP80 Preamp") (part "Resistor_10k"))
    )
    (comp (ref "R105")
      (value "47k")
      (fields
        (field (name "TOLERANCE") "1%")
        (field (name "MANUFACTURER") "Yageo")
        (field (name "POWER") "250mW")
      )
      (libsource (lib "CP80 Preamp") (part "Resistor_47k"))
    )
    (comp (ref "R106")
      (value "470k")
      (fields
        (field (name "MANUFACTURER") "Yageo")
        (field (name "POWER") "250mW")
        (field (name "TOLERANCE") "1%")
      )
      (libsource (lib "CP80 Preamp") (part "Resistor_470k"))
    )
    (comp (ref "R107")
      (value "3.3k")
      (fields
        (field (name "POWER") "250mW")
        (field (name "MANUFACTURER") "Yageo")
        (field (name "TOLERANCE") "1%")
      )
      (libsource (lib "CP80 Preamp") (part "Resistor_3k3"))
    )
    (comp (ref "R108")
      (value "5k6")
      (fields
        (field (name "MANUFACTURER") "Yageo")
        (field (name "POWER") "250mW")
        (field (name "TOLERANCE") "1%")
      )
      (libsource (lib "CP80 Preamp") (part "Resistor_5k6"))
    )
    (comp (ref "R109")
      (value "2k2")
      (fields
        (field (name "TOLERANCE") "1%")
        (field (name "MANUFACTURER") "Yageo")
        (field (name "POWER") "250mW")
      )
      (libsource (lib "CP80 Preamp") (part "Resistor_2k2"))
    )
    (comp (ref "R110")
      (value "8k2")
      (fields
        (field (name "TOLERANCE") "1%")
        (field (name "MANUFACTURER") "Yageo")
        (field (name "POWER") "250mW")
      )
      (libsource (lib "CP80 Preamp") (part "Resistor_8k2"))
    )
    (comp (ref "R111")
      (value "39k")
      (fields
        (field (name "TOLERANCE") "1%")
        (field (name "MANUFACTURER") "Yageo")
        (field (name "POWER") "250mW")
      )
      (libsource (lib "CP80 Preamp") (part "Resistor_39k"))
    )
    (comp (ref "R112")
      (value "39k")
      (fields
        (field (name "TOLERANCE") "1%")
        (field (name "MANUFACTURER") "Yageo")
        (field (name "POWER") "250mW")
      )
      (libsource (lib "CP80 Preamp") (part "Resistor_39k"))
    )
    (comp (ref "R113")
      (value "180k")
      (fields
        (field (name "TOLERANCE") "1%")
        (field (name "MANUFACTURER") "Yageo")
        (field (name "POWER") "250mW")
      )
      (libsource (lib "CP80 Preamp") (part "Resistor_180k"))
    )
    (comp (ref "R114")
      (value "220k")
      (fields
        (field (name "TOLERANCE") "1%")
        (field (name "MANUFACTURER") "Yageo")
        (field (name "POWER") "250mW")
      )
      (libsource (lib "CP80 Preamp") (part "Resistor_220k"))
    )
    (comp (ref "R115")
      (value "27k")
      (fields
        (field (name "TOLERANCE") "1%")
        (field (name "MANUFACTURER") "Yageo")
        (field (name "POWER") "250mW")
      )
      (libsource (lib "CP80 Preamp") (part "Resistor_27k"))
    )
    (comp (ref "R116")
      (value "10k")
      (fields
        (field (name "TOLERANCE") "1%")
        (field (name "POWER") "250mW")
        (field (name "MANUFACTURER") "Yageo")
      )
      (libsource (lib "CP80 Preamp") (part "Resistor_10k"))
    )
    (comp (ref "R117")
      (value "100k")
      (fields
        (field (name "TOLERANCE") "1%")
        (field (name "POWER") "250mW")
        (field (name "MANUFACTURER") "Yageo")
      )
      (libsource (lib "CP80 Preamp") (part "Resistor_100k"))
    )
    (comp (ref "R118")
      (value "330")
      (fields
        (field (name "TOLERANCE") "1%")
        (field (name "POWER") "250mW")
        (field (name "MANUFACTURER") "Yageo")
      )
      (libsource (lib "CP80 Preamp") (part "Resistor_330"))
    )
    (comp (ref "R119")
      (value "100k")
      (fields
        (field (name "TOLERANCE") "1%")
        (field (name "POWER") "250mW")
        (field (name "MANUFACTURER") "Yageo")
      )
      (libsource (lib "CP80 Preamp") (part "Resistor_100k"))
    )
    (comp (ref "R120")
      (value "2k2")
      (fields
        (field (name "TOLERANCE") "1%")
        (field (name "MANUFACTURER") "Yageo")
        (field (name "POWER") "250mW")
      )
      (libsource (lib "CP80 Preamp") (part "Resistor_2k2"))
    )
    (comp (ref "R121")
      (value "470k")
      (fields
        (field (name "MANUFACTURER") "Yageo")
        (field (name "POWER") "250mW")
        (field (name "TOLERANCE") "1%")
      )
      (libsource (lib "CP80 Preamp") (part "Resistor_470k"))
    )
    (comp (ref "R122")
      (value "1k")
      (fields
        (field (name "TOLERANCE") "1%")
        (field (name "MANUFACTURER") "Yageo")
        (field (name "POWER") "250mW")
      )
      (libsource (lib "CP80 Preamp") (part "Resistor_1k"))
    )
    (comp (ref "R123")
      (value "220k")
      (fields
        (field (name "TOLERANCE") "1%")
        (field (name "MANUFACTURER") "Yageo")
        (field (name "POWER") "250mW")
      )
      (libsource (lib "CP80 Preamp") (part "Resistor_220k"))
    )
    (comp (ref "R124")
      (value "330")
      (fields
        (field (name "TOLERANCE") "1%")
        (field (name "POWER") "250mW")
        (field (name "MANUFACTURER") "Yageo")
      )
      (libsource (lib "CP80 Preamp") (part "Resistor_330"))
    )
    (comp (ref "R125")
      (value "47k")
      (fields
        (field (name "TOLERANCE") "1%")
        (field (name "MANUFACTURER") "Yageo")
        (field (name "POWER") "250mW")
      )
      (libsource (lib "CP80 Preamp") (part "Resistor_47k"))
    )
    (comp (ref "R126")
      (value "5k6")
      (fields
        (field (name "MANUFACTURER") "Yageo")
        (field (name "POWER") "250mW")
        (field (name "TOLERANCE") "1%")
      )
      (libsource (lib "CP80 Preamp") (part "Resistor_5k6"))
    )
    (comp (ref "R127")
      (value "180k")
      (fields
        (field (name "TOLERANCE") "1%")
        (field (name "MANUFACTURER") "Yageo")
        (field (name "POWER") "250mW")
      )
      (libsource (lib "CP80 Preamp") (part "Resistor_180k"))
    )
    (comp (ref "R128")
      (value "180k")
      (fields
        (field (name "TOLERANCE") "1%")
        (field (name "MANUFACTURER") "Yageo")
        (field (name "POWER") "250mW")
      )
      (libsource (lib "CP80 Preamp") (part "Resistor_180k"))
    )
    (comp (ref "R129")
      (value "27k")
      (fields
        (field (name "TOLERANCE") "1%")
        (field (name "MANUFACTURER") "Yageo")
        (field (name "POWER") "250mW")
      )
      (libsource (lib "CP80 Preamp") (part "Resistor_27k"))
    )
    (comp (ref "R130")
      (value "100k")
      (fields
        (field (name "TOLERANCE") "1%")
        (field (name "POWER") "250mW")
        (field (name "MANUFACTURER") "Yageo")
      )
      (libsource (lib "CP80 Preamp") (part "Resistor_100k"))
    )
    (comp (ref "R131")
      (value "220k")
      (fields
        (field (name "TOLERANCE") "1%")
        (field (name "MANUFACTURER") "Yageo")
        (field (name "POWER") "250mW")
      )
      (libsource (lib "CP80 Preamp") (part "Resistor_220k"))
    )
    (comp (ref "R132")
      (value "27k")
      (fields
        (field (name "TOLERANCE") "1%")
        (field (name "MANUFACTURER") "Yageo")
        (field (name "POWER") "250mW")
      )
      (libsource (lib "CP80 Preamp") (part "Resistor_27k"))
    )
    (comp (ref "R133")
      (value "100k")
      (fields
        (field (name "TOLERANCE") "1%")
        (field (name "POWER") "250mW")
        (field (name "MANUFACTURER") "Yageo")
      )
      (libsource (lib "CP80 Preamp") (part "Resistor_100k"))
    )
    (comp (ref "R134")
      (value "39k")
      (fields
        (field (name "TOLERANCE") "1%")
        (field (name "MANUFACTURER") "Yageo")
        (field (name "POWER") "250mW")
      )
      (libsource (lib "CP80 Preamp") (part "Resistor_39k"))
    )
    (comp (ref "R135")
      (value "22k")
      (fields
        (field (name "TOLERANCE") "1%")
        (field (name "POWER") "250mW")
        (field (name "MANUFACTURER") "Yageo")
      )
      (libsource (lib "CP80 Preamp") (part "Resistor_22k"))
    )
    (comp (ref "R136")
      (value "22k")
      (fields
        (field (name "TOLERANCE") "1%")
        (field (name "POWER") "250mW")
        (field (name "MANUFACTURER") "Yageo")
      )
      (libsource (lib "CP80 Preamp") (part "Resistor_22k"))
    )
    (comp (ref "R137")
      (value "180k")
      (fields
        (field (name "TOLERANCE") "1%")
        (field (name "MANUFACTURER") "Yageo")
        (field (name "POWER") "250mW")
      )
      (libsource (lib "CP80 Preamp") (part "Resistor_180k"))
    )
    (comp (ref "R138")
      (value "220k")
      (fields
        (field (name "TOLERANCE") "1%")
        (field (name "MANUFACTURER") "Yageo")
        (field (name "POWER") "250mW")
      )
      (libsource (lib "CP80 Preamp") (part "Resistor_220k"))
    )
    (comp (ref "R139")
      (value "27k")
      (fields
        (field (name "TOLERANCE") "1%")
        (field (name "MANUFACTURER") "Yageo")
        (field (name "POWER") "250mW")
      )
      (libsource (lib "CP80 Preamp") (part "Resistor_27k"))
    )
    (comp (ref "R140")
      (value "100k")
      (fields
        (field (name "TOLERANCE") "1%")
        (field (name "POWER") "250mW")
        (field (name "MANUFACTURER") "Yageo")
      )
      (libsource (lib "CP80 Preamp") (part "Resistor_100k"))
    )
    (comp (ref "R141")
      (value "180k")
      (fields
        (field (name "TOLERANCE") "1%")
        (field (name "MANUFACTURER") "Yageo")
        (field (name "POWER") "250mW")
      )
      (libsource (lib "CP80 Preamp") (part "Resistor_180k"))
    )
    (comp (ref "R142")
      (value "220k")
      (fields
        (field (name "TOLERANCE") "1%")
        (field (name "MANUFACTURER") "Yageo")
        (field (name "POWER") "250mW")
      )
      (libsource (lib "CP80 Preamp") (part "Resistor_220k"))
    )
    (comp (ref "R143")
      (value "27k")
      (fields
        (field (name "TOLERANCE") "1%")
        (field (name "MANUFACTURER") "Yageo")
        (field (name "POWER") "250mW")
      )
      (libsource (lib "CP80 Preamp") (part "Resistor_27k"))
    )
    (comp (ref "R144")
      (value "100k")
      (fields
        (field (name "TOLERANCE") "1%")
        (field (name "POWER") "250mW")
        (field (name "MANUFACTURER") "Yageo")
      )
      (libsource (lib "CP80 Preamp") (part "Resistor_100k"))
    )
    (comp (ref "R145")
      (value "180k")
      (fields
        (field (name "TOLERANCE") "1%")
        (field (name "MANUFACTURER") "Yageo")
        (field (name "POWER") "250mW")
      )
      (libsource (lib "CP80 Preamp") (part "Resistor_180k"))
    )
    (comp (ref "R146")
      (value "220k")
      (fields
        (field (name "TOLERANCE") "1%")
        (field (name "MANUFACTURER") "Yageo")
        (field (name "POWER") "250mW")
      )
      (libsource (lib "CP80 Preamp") (part "Resistor_220k"))
    )
    (comp (ref "R147")
      (value "27k")
      (fields
        (field (name "TOLERANCE") "1%")
        (field (name "MANUFACTURER") "Yageo")
        (field (name "POWER") "250mW")
      )
      (libsource (lib "CP80 Preamp") (part "Resistor_27k"))
    )
    (comp (ref "R148")
      (value "100k")
      (fields
        (field (name "TOLERANCE") "1%")
        (field (name "POWER") "250mW")
        (field (name "MANUFACTURER") "Yageo")
      )
      (libsource (lib "CP80 Preamp") (part "Resistor_100k"))
    )
    (comp (ref "R149")
      (value "330")
      (fields
        (field (name "TOLERANCE") "1%")
        (field (name "POWER") "250mW")
        (field (name "MANUFACTURER") "Yageo")
      )
      (libsource (lib "CP80 Preamp") (part "Resistor_330"))
    )
    (comp (ref "R150")
      (value "330")
      (fields
        (field (name "TOLERANCE") "1%")
        (field (name "POWER") "250mW")
        (field (name "MANUFACTURER") "Yageo")
      )
      (libsource (lib "CP80 Preamp") (part "Resistor_330"))
    )
    (comp (ref "R151")
      (value "2k2")
      (fields
        (field (name "TOLERANCE") "1%")
        (field (name "POWER") "250mW")
        (field (name "MANUFACTURER") "Yageo")
      )
      (libsource (lib "CP80 Preamp") (part "Resistor_2k2"))
    )
    (comp (ref "R152")
      (value "10k")
      (fields
        (field (name "TOLERANCE") "1%")
        (field (name "POWER") "250mW")
        (field (name "MANUFACTURER") "Yageo")
      )
      (libsource (lib "CP80 Preamp") (part "Resistor_10k"))
    )
    (comp (ref "R153")
      (value "2k2")
      (fields
        (field (name "TOLERANCE") "1%")
        (field (name "POWER") "250mW")
        (field (name "MANUFACTURER") "Yageo")
      )
      (libsource (lib "CP80 Preamp") (part "Resistor_2k2"))
    )
    (comp (ref "R154")
      (value "100k")
      (fields
        (field (name "TOLERANCE") "1%")
        (field (name "POWER") "250mW")
        (field (name "MANUFACTURER") "Yageo")
      )
      (libsource (lib "CP80 Preamp") (part "Resistor_100k"))
    )
    (comp (ref "R155")
      (value "100k")
      (fields
        (field (name "TOLERANCE") "1%")
        (field (name "POWER") "250mW")
        (field (name "MANUFACTURER") "Yageo")
      )
      (libsource (lib "CP80 Preamp") (part "Resistor_100k"))
    )
    (comp (ref "R156")
      (value "39k")
      (fields
        (field (name "TOLERANCE") "1%")
        (field (name "POWER") "250mW")
        (field (name "MANUFACTURER") "Yageo")
      )
      (libsource (lib "CP80 Preamp") (part "Resistor_39k"))
    )
    (comp (ref "R157")
      (value "39k")
      (fields
        (field (name "TOLERANCE") "1%")
        (field (name "POWER") "250mW")
        (field (name "MANUFACTURER") "Yageo")
      )
      (libsource (lib "CP80 Preamp") (part "Resistor_39k"))
    )
    (comp (ref "R158")
      (value "5k6")
      (fields
        (field (name "TOLERANCE") "1%")
        (field (name "POWER") "250mW")
        (field (name "MANUFACTURER") "Yageo")
      )
      (libsource (lib "CP80 Preamp") (part "Resistor_5k6"))
    )
    (comp (ref "R159")
      (value "39k")
      (fields
        (field (name "TOLERANCE") "1%")
        (field (name "POWER") "250mW")
        (field (name "MANUFACTURER") "Yageo")
      )
      (libsource (lib "CP80 Preamp") (part "Resistor_39k"))
    )
    (comp (ref "R160")
      (value "39k")
      (fields
        (field (name "TOLERANCE") "1%")
        (field (name "POWER") "250mW")
        (field (name "MANUFACTURER") "Yageo")
      )
      (libsource (lib "CP80 Preamp") (part "Resistor_39k"))
    )
    (comp (ref "R161")
      (value "5k6")
      (fields
        (field (name "TOLERANCE") "1%")
        (field (name "POWER") "250mW")
        (field (name "MANUFACTURER") "Yageo")
      )
      (libsource (lib "CP80 Preamp") (part "Resistor_5k6"))
    )
    (comp (ref "R162")
      (value "10k")
      (fields
        (field (name "TOLERANCE") "1%")
        (field (name "POWER") "250mW")
        (field (name "MANUFACTURER") "Yageo")
      )
      (libsource (lib "CP80 Preamp") (part "Resistor_10k"))
    )
    (comp (ref "R201")
      (value "100")
      (fields
        (field (name "TOLERANCE") "1%")
        (field (name "POWER") "250mW")
        (field (name "MANUFACTURER") "Yageo")
      )
      (libsource (lib "CP80 Preamp") (part "Resistor_100"))
    )
    (comp (ref "R202")
      (value "1k2")
      (fields
        (field (name "TOLERANCE") "1%")
        (field (name "POWER") "250mW")
        (field (name "MANUFACTURER") "Yageo")
      )
      (libsource (lib "CP80 Preamp") (part "Resistor_1k2"))
    )
    (comp (ref "R203")
      (value "100")
      (fields
        (field (name "TOLERANCE") "1%")
        (field (name "POWER") "250mW")
        (field (name "MANUFACTURER") "Yageo")
      )
      (libsource (lib "CP80 Preamp") (part "Resistor_100"))
    )
    (comp (ref "R204")
      (value "2k2")
      (fields
        (field (name "TOLERANCE") "1%")
        (field (name "POWER") "250mW")
        (field (name "MANUFACTURER") "Yageo")
      )
      (libsource (lib "CP80 Preamp") (part "Resistor_2k2"))
    )
    (comp (ref "R205")
      (value "2k2")
      (fields
        (field (name "TOLERANCE") "1%")
        (field (name "POWER") "250mW")
        (field (name "MANUFACTURER") "Yageo")
      )
      (libsource (lib "CP80 Preamp") (part "Resistor_2k2"))
    )
    (comp (ref "R206")
      (value "5k6")
      (fields
        (field (name "TOLERANCE") "1%")
        (field (name "POWER") "250mW")
        (field (name "MANUFACTURER") "Yageo")
      )
      (libsource (lib "CP80 Preamp") (part "Resistor_5k6"))
    )
    (comp (ref "RS1")
      (value "47k")
      (fields
        (field (name "TOLERANCE") "1%")
        (field (name "MANUFACTURER") "Yageo")
        (field (name "POWER") "250mW")
      )
      (libsource (lib "CP80 Preamp") (part "Resistor_47k"))
    )
    (comp (ref "RS2")
      (value "4k7")
      (fields
        (field (name "TOLERANCE") "1%")
        (field (name "MANUFACTURER") "Yageo")
        (field (name "POWER") "250mW")
      )
      (libsource (lib "CP80 Preamp") (part "Resistor_4k7"))
    )
    (comp (ref "S1")
      (value "Lever Switch")
      (description "Lever Switch, 2P3T - Unknown replacement as of yet.")
      (fields (field (name "MANUFACTURER") "UNK"))
      (libsource (lib "CP80 Preamp") (part "Switch, Lever, 2P3T"))
    )
    (comp (ref "S2")
      (value "Switch, Toggle, DPST")
      (description "This is a specialized switch with no known replacement. Will research more.")
      (libsource (lib "CP80 Preamp") (part "Switch, Toggle, DPST"))
    )
    (comp (ref "TR101")
      (value "BC549BTA")
      (footprint "SOT95P237X111-3N")
      (fields (field (name "PART NUMBER") "2SC458C") (field (name "MANUFACTURER") "Hitachi"))
      (libsource (lib "CP80 Preamp") (part "Transistor, NPN, 30V, 0.1A, 500mW, TO-92"))
    )
    (comp (ref "TR102")
      (value "BC549BTA")
      (footprint "SOT95P237X111-3N")
      (fields (field (name "PART NUMBER") "2SC458C") (field (name "MANUFACTURER") "Hitachi"))
      (libsource (lib "CP80 Preamp") (part "Transistor, NPN, 30V, 0.1A, 500mW, TO-92"))
    )
    (comp (ref "TR201")
      (value "BC549BTA")
      (footprint "SOT95P237X111-3N")
      (fields (field (name "PART NUMBER") "2SC458C") (field (name "MANUFACTURER") "Hitachi"))
      (libsource (lib "CP80 Preamp") (part "Transistor, NPN, 30V, 0.1A, 500mW, TO-92"))
    )
    (comp (ref "TRD101")
      (value "NSL-32SR2S")
      (footprint "SODFL370X135-2N")
      (fields (field (name "MANUFACTURER") "Silicon Sensors Inc") (field (name "PART NUMBER") "MCD-527"))
      (libsource (lib "") (part "LDR (Light Dependant Resistor)_1"))
    )
    (comp (ref "TRD102")
      (value "NSL-32SR2S")
      (footprint "SODFL370X135-2N")
      (fields (field (name "MANUFACTURER") "Silicon Sensors Inc") (field (name "PART NUMBER") "MCD-527"))
      (libsource (lib "CP80 Preamp") (part "LDR (Light Dependant Resistor)"))
    )
    (comp (ref "U102")
      (value "RC4558IP")
      (fields (field (name "PARTNUMBER") "RC4558PWR") (field (name "MANUFACTURER") "Texas Instruments"))
      (libsource (lib "CP80 Preamp") (part "IC, OPAMP, GP, 2 Circuit, 8DIP"))
    )
    (comp (ref "VR1")
      (value "B100K x 2")
      (footprint "SODFL370X135-2N")
      (fields
        (field (name "MANUFACTURER") "Various")
        (field (name "POWER") "125mW")
        (field (name "TOLERANCE") "20%")
      )
      (libsource (lib "CP80 Preamp") (part "Pot, Dual, Carbon, 100k, Lin"))
    )
    (comp (ref "VR2")
      (value "A50k")
      (fields
        (field (name "MANUFACTURER") "Various")
        (field (name "POWER") "200mW")
        (field (name "TOLERANCE") "20%")
      )
      (libsource (lib "CP80 Preamp") (part "Pot, Single, Cond Plastic, 50k, Log"))
    )
    (comp (ref "VR3")
      (value "A1k")
      (fields
        (field (name "MANUFACTURER") "Bourns")
        (field (name "POWER") "250mW")
        (field (name "TOLERANCE") "20%")
      )
      (libsource (lib "CP80 Preamp") (part "Pot, Single, Cond Plastic, 1k, Log"))
    )
    (comp (ref "VR4")
      (value "10k Linear")
      (footprint "SMD RES 1kO 20% .250W 200V 2420-Footprint-1")
      (fields
        (field (name "MANUFACTURER") "Various")
        (field (name "POWER") ".2mW")
        (field (name "TOLERANCE") "20%")
      )
      (libsource (lib "CP80 Preamp") (part "Pot, Single, Cond Plastic, 10k"))
    )
    (comp (ref "VR5")
      (value "20K x 2")
      (footprint "SODFL370X135-2N")
      (fields
        (field (name "MANUFACTURER") "Various")
        (field (name "POWER") "125mW")
        (field (name "TOLERANCE") "20%")
      )
      (libsource (lib "CP80 Preamp") (part "Pot, Dual, Cermet, 20K"))
    )
    (comp (ref "VR6")
      (value "PDB182-K220K-104B")
      (footprint "SODFL370X135-2N")
      (fields
        (field (name "MANUFACTURER") "Various")
        (field (name "POWER") "125mW")
        (field (name "TOLERANCE") "20%")
      )
      (libsource (lib "CP80 Preamp") (part "Pot, Dual, Carbon, 100k, Lin"))
    )
    (comp (ref "VR7")
      (value "B22k")
      (footprint "SMD RES 1kO 20% .250W 200V 2420-Footprint-1")
      (fields
        (field (name "MANUFACTURER") "Various")
        (field (name "POWER") "250mW")
        (field (name "TOLERANCE") "20%")
      )
      (libsource (lib "CP80 Preamp") (part "Pot, Trim, Cermet, 25k, Lin"))
    )
    (comp (ref "VR8")
      (value "B100k")
      (fields
        (field (name "MANUFACTURER") "Various")
        (field (name "POWER") "250mW")
        (field (name "TOLERANCE") "20%")
      )
      (libsource (lib "CP80 Preamp") (part "Pot, Trim, Cermet, 100k, Lin"))
    )
    (comp (ref "VR9")
      (value "B100k")
      (fields
        (field (name "MANUFACTURER") "Various")
        (field (name "POWER") "250mW")
        (field (name "TOLERANCE") "20%")
      )
      (libsource (lib "CP80 Preamp") (part "Pot, Trim, Cermet, 100k, Lin"))
    )
    (comp (ref "VR10")
      (value "B100k")
      (fields
        (field (name "MANUFACTURER") "Various")
        (field (name "POWER") "250mW")
        (field (name "TOLERANCE") "20%")
      )
      (libsource (lib "CP80 Preamp") (part "Pot, Trim, Cermet, 100k, Lin"))
    )
    (comp (ref "VR11")
      (value "B100k")
      (fields
        (field (name "MANUFACTURER") "Various")
        (field (name "POWER") "250mW")
        (field (name "TOLERANCE") "20%")
      )
      (libsource (lib "CP80 Preamp") (part "Pot, Trim, Cermet, 100k, Lin"))
    )
    (comp (ref "VR12")
      (value "B10k")
      (fields
        (field (name "MANUFACTURER") "Various")
        (field (name "POWER") "125mw")
        (field (name "TOLERANCE") "20%")
      )
      (libsource (lib "CP80 Preamp") (part "Pot, Trim, Cermet, 10k, Lin"))
    )
  )
  (nets
    (net (code "1") (name "+8V0") (class "Default")
      (node (ref "C127") (pin "1") (pinfunction "1_1") (pintype "passive"))
      (node (ref "C203") (pin "N") (pinfunction "N_N") (pintype "passive"))
      (node (ref "C204") (pin "P") (pinfunction "P_P") (pintype "passive"))
      (node (ref "D102") (pin "A") (pinfunction "A_A") (pintype "passive"))
      (node (ref "R159") (pin "2") (pinfunction "2_2") (pintype "passive"))
      (node (ref "R204") (pin "1") (pinfunction "1_1") (pintype "passive"))
      (node (ref "R205") (pin "2") (pinfunction "2_2") (pintype "passive"))
      (node (ref "VR11") (pin "3") (pinfunction "3_3") (pintype "passive"))
      (node (ref "VR7") (pin "1") (pinfunction "1_1") (pintype "passive"))
      (node (ref "VR7") (pin "2") (pinfunction "2_2") (pintype "passive"))
      (node (ref "VR9") (pin "3") (pinfunction "3_3") (pintype "passive"))
    )
    (net (code "2") (name "+12V0") (class "Default")
      (node (ref "FET3") (pin "3") (pinfunction "D_3") (pintype "passive"))
      (node (ref "FET5") (pin "3") (pinfunction "D_3") (pintype "passive"))
      (node (ref "FET6") (pin "3") (pinfunction "D_3") (pintype "passive"))
      (node (ref "FET7") (pin "3") (pinfunction "D_3") (pintype "passive"))
      (node (ref "FET8") (pin "3") (pinfunction "D_3") (pintype "passive"))
      (node (ref "FET9") (pin "3") (pinfunction "D_3") (pintype "passive"))
      (node (ref "R104") (pin "2") (pinfunction "2_2") (pintype "passive"))
      (node (ref "R105") (pin "1") (pinfunction "1_1") (pintype "passive"))
      (node (ref "R110") (pin "1") (pinfunction "1_1") (pintype "passive"))
      (node (ref "R113") (pin "1") (pinfunction "1_1") (pintype "passive"))
      (node (ref "R125") (pin "1") (pinfunction "1_1") (pintype "passive"))
      (node (ref "R126") (pin "1") (pinfunction "1_1") (pintype "passive"))
      (node (ref "R127") (pin "1") (pinfunction "1_1") (pintype "passive"))
      (node (ref "R128") (pin "1") (pinfunction "1_1") (pintype "passive"))
      (node (ref "R137") (pin "1") (pinfunction "1_1") (pintype "passive"))
      (node (ref "R141") (pin "1") (pinfunction "1_1") (pintype "passive"))
      (node (ref "R145") (pin "1") (pinfunction "1_1") (pintype "passive"))
      (node (ref "TR201") (pin "2") (pinfunction "2_2") (pintype "passive"))
    )
    (net (code "3") (name "+16V0") (class "Default")
      (node (ref "C203") (pin "P") (pinfunction "P_P") (pintype "passive"))
      (node (ref "D201") (pin "C") (pinfunction "C_C") (pintype "passive"))
      (node (ref "R152") (pin "1") (pinfunction "1_1") (pintype "passive"))
      (node (ref "R162") (pin "1") (pinfunction "1_1") (pintype "passive"))
      (node (ref "R203") (pin "1") (pinfunction "1_1") (pintype "passive"))
      (node (ref "R205") (pin "1") (pinfunction "1_1") (pintype "passive"))
      (node (ref "TRD101") (pin "3") (pinfunction "3_3") (pintype "passive"))
      (node (ref "TRD102") (pin "3") (pinfunction "3_3") (pintype "passive"))
      (node (ref "U102") (pin "8") (pinfunction "8_8") (pintype "passive"))
    )
    (net (code "4") (name "GND") (class "Default")
      (node (ref "BH-C128") (pin "1") (pinfunction "1_1") (pintype "passive"))
      (node (ref "BH-C129") (pin "1") (pinfunction "1_1") (pintype "passive"))
      (node (ref "BH-R134") (pin "1") (pinfunction "1_1") (pintype "passive"))
      (node (ref "BH-VR3") (pin "2") (pinfunction "2_2") (pintype "passive"))
      (node (ref "BL-C109") (pin "1") (pinfunction "1_1") (pintype "passive"))
      (node (ref "BL-C128") (pin "1") (pinfunction "1_1") (pintype "passive"))
      (node (ref "BL-R143") (pin "1") (pinfunction "1_1") (pintype "passive"))
      (node (ref "BL-VR3") (pin "2") (pinfunction "2_2") (pintype "passive"))
      (node (ref "BM-C128") (pin "1") (pinfunction "1_1") (pintype "passive"))
      (node (ref "BM-C129") (pin "1") (pinfunction "1_1") (pintype "passive"))
      (node (ref "BM-R143") (pin "1") (pinfunction "1_1") (pintype "passive"))
      (node (ref "BM-VR3") (pin "2") (pinfunction "2_2") (pintype "passive"))
      (node (ref "BM-VR3") (pin "3") (pinfunction "3_3") (pintype "passive"))
      (node (ref "C105") (pin "N") (pinfunction "N_N") (pintype "passive"))
      (node (ref "C108") (pin "1") (pinfunction "1_1") (pintype "passive"))
      (node (ref "C128") (pin "1") (pinfunction "1_1") (pintype "passive"))
      (node (ref "C129") (pin "1") (pinfunction "1_1") (pintype "passive"))
      (node (ref "C130") (pin "1") (pinfunction "1_1") (pintype "passive"))
      (node (ref "C131") (pin "1") (pinfunction "1_1") (pintype "passive"))
      (node (ref "C201") (pin "N") (pinfunction "N_N") (pintype "passive"))
      (node (ref "C202") (pin "1") (pinfunction "1_1") (pintype "passive"))
      (node (ref "C204") (pin "N") (pinfunction "N_N") (pintype "passive"))
      (node (ref "D1") (pin "2") (pinfunction "K_2") (pintype "passive"))
      (node (ref "D201") (pin "A") (pinfunction "A_A") (pintype "passive"))
      (node (ref "D202") (pin "C") (pinfunction "C_C") (pintype "passive"))
      (node (ref "J1") (pin "1") (pinfunction "1_1") (pintype "passive"))
      (node (ref "J1") (pin "3") (pinfunction "3_3") (pintype "passive"))
      (node (ref "J2") (pin "1") (pinfunction "1_1") (pintype "passive"))
      (node (ref "J2") (pin "3") (pinfunction "3_3") (pintype "passive"))
      (node (ref "J201") (pin "0") (pinfunction "0_0") (pintype "passive"))
      (node (ref "LT1") (pin "0") (pinfunction "0_0") (pintype "passive"))
      (node (ref "LT2") (pin "0") (pinfunction "0_0") (pintype "passive"))
      (node (ref "R102") (pin "1") (pinfunction "1_1") (pintype "passive"))
      (node (ref "R103") (pin "1") (pinfunction "1_1") (pintype "passive"))
      (node (ref "R108") (pin "1") (pinfunction "1_1") (pintype "passive"))
      (node (ref "R109") (pin "2") (pinfunction "2_2") (pintype "passive"))
      (node (ref "R114") (pin "2") (pinfunction "2_2") (pintype "passive"))
      (node (ref "R115") (pin "2") (pinfunction "2_2") (pintype "passive"))
      (node (ref "R117") (pin "1") (pinfunction "1_1") (pintype "passive"))
      (node (ref "R119") (pin "1") (pinfunction "1_1") (pintype "passive"))
      (node (ref "R120") (pin "2") (pinfunction "2_2") (pintype "passive"))
      (node (ref "R122") (pin "1") (pinfunction "1_1") (pintype "passive"))
      (node (ref "R123") (pin "2") (pinfunction "2_2") (pintype "passive"))
      (node (ref "R129") (pin "2") (pinfunction "2_2") (pintype "passive"))
      (node (ref "R130") (pin "1") (pinfunction "1_1") (pintype "passive"))
      (node (ref "R131") (pin "2") (pinfunction "2_2") (pintype "passive"))
      (node (ref "R132") (pin "2") (pinfunction "2_2") (pintype "passive"))
      (node (ref "R133") (pin "1") (pinfunction "1_1") (pintype "passive"))
      (node (ref "R134") (pin "1") (pinfunction "1_1") (pintype "passive"))
      (node (ref "R138") (pin "2") (pinfunction "2_2") (pintype "passive"))
      (node (ref "R139") (pin "2") (pinfunction "2_2") (pintype "passive"))
      (node (ref "R140") (pin "1") (pinfunction "1_1") (pintype "passive"))
      (node (ref "R142") (pin "2") (pinfunction "2_2") (pintype "passive"))
      (node (ref "R143") (pin "2") (pinfunction "2_2") (pintype "passive"))
      (node (ref "R144") (pin "1") (pinfunction "1_1") (pintype "passive"))
      (node (ref "R146") (pin "2") (pinfunction "2_2") (pintype "passive"))
      (node (ref "R147") (pin "2") (pinfunction "2_2") (pintype "passive"))
      (node (ref "R148") (pin "1") (pinfunction "1_1") (pintype "passive"))
      (node (ref "R151") (pin "2") (pinfunction "2_2") (pintype "passive"))
      (node (ref "R153") (pin "2") (pinfunction "2_2") (pintype "passive"))
      (node (ref "R154") (pin "2") (pinfunction "2_2") (pintype "passive"))
      (node (ref "R155") (pin "2") (pinfunction "2_2") (pintype "passive"))
      (node (ref "R161") (pin "2") (pinfunction "2_2") (pintype "passive"))
      (node (ref "R204") (pin "2") (pinfunction "2_2") (pintype "passive"))
      (node (ref "U102") (pin "4") (pinfunction "4_4") (pintype "passive"))
      (node (ref "VR1") (pin "0") (pinfunction "0_0") (pintype "passive"))
      (node (ref "VR12") (pin "3") (pinfunction "3_3") (pintype "passive"))
      (node (ref "VR3") (pin "2") (pinfunction "2_2") (pintype "passive"))
      (node (ref "VR5") (pin "0") (pinfunction "0_0") (pintype "passive"))
    )
    (net (code "5") (name "Net-(BH-C102-Pad1)") (class "Default")
      (node (ref "BH-C102") (pin "1") (pinfunction "1_1") (pintype "passive"))
      (node (ref "BH-R116") (pin "2") (pinfunction "2_2") (pintype "passive"))
    )
    (net (code "6") (name "Net-(BH-C102-Pad2)") (class "Default")
      (node (ref "BH-C102") (pin "2") (pinfunction "2_2") (pintype "passive"))
      (node (ref "BH-R107") (pin "1") (pinfunction "1_1") (pintype "passive"))
    )
    (net (code "7") (name "Net-(BH-C103-Pad1)") (class "Default")
      (node (ref "BH-C103") (pin "1") (pinfunction "1_1") (pintype "passive"))
      (node (ref "BH-C128") (pin "2") (pinfunction "2_2") (pintype "passive"))
      (node (ref "BH-C129") (pin "2") (pinfunction "2_2") (pintype "passive"))
      (node (ref "BH-R107") (pin "2") (pinfunction "2_2") (pintype "passive"))
      (node (ref "BH-VR4") (pin "1") (pinfunction "1_1") (pintype "passive"))
    )
    (net (code "8") (name "Net-(BH-C110-PadN)") (class "Default")
      (node (ref "BH-C110") (pin "N") (pinfunction "N_N") (pintype "passive"))
      (node (ref "BH-RS1") (pin "2") (pinfunction "2_2") (pintype "passive"))
      (node (ref "BH-VR2") (pin "1") (pinfunction "1_1") (pintype "passive"))
      (node (ref "BH-VR4") (pin "3") (pinfunction "3_3") (pintype "passive"))
    )
    (net (code "9") (name "Net-(BH-C110-PadP)") (class "Default")
      (node (ref "BH-C110") (pin "P") (pinfunction "P_P") (pintype "passive"))
      (node (ref "BH-C111") (pin "P") (pinfunction "P_P") (pintype "passive"))
      (node (ref "BH-R116") (pin "1") (pinfunction "1_1") (pintype "passive"))
    )
    (net (code "10") (name "Net-(BH-C111-PadN)") (class "Default")
      (node (ref "BH-C111") (pin "N") (pinfunction "N_N") (pintype "passive"))
      (node (ref "BH-R134") (pin "2") (pinfunction "2_2") (pintype "passive"))
      (node (ref "BH-VR2") (pin "2") (pinfunction "2_2") (pintype "passive"))
      (node (ref "BH-VR2") (pin "3") (pinfunction "3_3") (pintype "passive"))
      (node (ref "BH-VR3") (pin "1") (pinfunction "1_1") (pintype "passive"))
    )
    (net (code "11") (name "Net-(BH-RS1-Pad1)") (class "Default")
      (node (ref "BH-RS1") (pin "1") (pinfunction "1_1") (pintype "passive"))
      (node (ref "BH-RS2") (pin "2") (pinfunction "2_2") (pintype "passive"))
    )
    (net (code "12") (name "Net-(BH-RS2-Pad1)") (class "Default")
      (node (ref "BH-RS2") (pin "1") (pinfunction "1_1") (pintype "passive"))
      (node (ref "BH-VR4") (pin "2") (pinfunction "2_2") (pintype "passive"))
    )
    (net (code "13") (name "Net-(BL-C102-Pad1)") (class "Default")
      (node (ref "BL-C102") (pin "1") (pinfunction "1_1") (pintype "passive"))
      (node (ref "BL-R116") (pin "2") (pinfunction "2_2") (pintype "passive"))
    )
    (net (code "14") (name "Net-(BL-C102-Pad2)") (class "Default")
      (node (ref "BL-C102") (pin "2") (pinfunction "2_2") (pintype "passive"))
      (node (ref "BL-R107") (pin "1") (pinfunction "1_1") (pintype "passive"))
    )
    (net (code "15") (name "Net-(BL-C103-Pad1)") (class "Default")
      (node (ref "BL-C103") (pin "1") (pinfunction "1_1") (pintype "passive"))
      (node (ref "BL-C109") (pin "2") (pinfunction "2_2") (pintype "passive"))
      (node (ref "BL-RS1") (pin "1") (pinfunction "1_1") (pintype "passive"))
      (node (ref "BL-RS2") (pin "2") (pinfunction "2_2") (pintype "passive"))
    )
    (net (code "16") (name "Net-(BL-C110-PadN)") (class "Default")
      (node (ref "BL-C110") (pin "N") (pinfunction "N_N") (pintype "passive"))
      (node (ref "BL-RS1") (pin "2") (pinfunction "2_2") (pintype "passive"))
      (node (ref "BL-VR2") (pin "1") (pinfunction "1_1") (pintype "passive"))
      (node (ref "BL-VR4") (pin "3") (pinfunction "3_3") (pintype "passive"))
    )
    (net (code "17") (name "Net-(BL-C110-PadP)") (class "Default")
      (node (ref "BL-C110") (pin "P") (pinfunction "P_P") (pintype "passive"))
      (node (ref "BL-C111") (pin "P") (pinfunction "P_P") (pintype "passive"))
      (node (ref "BL-R116") (pin "1") (pinfunction "1_1") (pintype "passive"))
    )
    (net (code "18") (name "Net-(BL-C111-PadN)") (class "Default")
      (node (ref "BL-C111") (pin "N") (pinfunction "N_N") (pintype "passive"))
      (node (ref "BL-R143") (pin "2") (pinfunction "2_2") (pintype "passive"))
      (node (ref "BL-VR2") (pin "2") (pinfunction "2_2") (pintype "passive"))
      (node (ref "BL-VR2") (pin "3") (pinfunction "3_3") (pintype "passive"))
      (node (ref "BL-VR3") (pin "1") (pinfunction "1_1") (pintype "passive"))
      (node (ref "BL-VR3") (pin "3") (pinfunction "3_3") (pintype "passive"))
    )
    (net (code "19") (name "Net-(BL-C128-Pad2)") (class "Default")
      (node (ref "BL-C128") (pin "2") (pinfunction "2_2") (pintype "passive"))
      (node (ref "BL-R107") (pin "2") (pinfunction "2_2") (pintype "passive"))
      (node (ref "BL-VR4") (pin "1") (pinfunction "1_1") (pintype "passive"))
    )
    (net (code "20") (name "Net-(BL-RS2-Pad1)") (class "Default")
      (node (ref "BL-RS2") (pin "1") (pinfunction "1_1") (pintype "passive"))
      (node (ref "BL-VR4") (pin "2") (pinfunction "2_2") (pintype "passive"))
    )
    (net (code "21") (name "Net-(BM-C102-Pad1)") (class "Default")
      (node (ref "BM-C102") (pin "1") (pinfunction "1_1") (pintype "passive"))
      (node (ref "BM-R116") (pin "2") (pinfunction "2_2") (pintype "passive"))
    )
    (net (code "22") (name "Net-(BM-C102-Pad2)") (class "Default")
      (node (ref "BM-C102") (pin "2") (pinfunction "2_2") (pintype "passive"))
      (node (ref "BM-R107") (pin "1") (pinfunction "1_1") (pintype "passive"))
    )
    (net (code "23") (name "Net-(BM-C103-Pad1)") (class "Default")
      (node (ref "BM-C103") (pin "1") (pinfunction "1_1") (pintype "passive"))
      (node (ref "BM-C129") (pin "2") (pinfunction "2_2") (pintype "passive"))
      (node (ref "BM-RS2") (pin "1") (pinfunction "1_1") (pintype "passive"))
      (node (ref "BM-VR4") (pin "2") (pinfunction "2_2") (pintype "passive"))
    )
    (net (code "24") (name "Net-(BM-C110-PadN)") (class "Default")
      (node (ref "BM-C110") (pin "N") (pinfunction "N_N") (pintype "passive"))
      (node (ref "BM-RS1") (pin "2") (pinfunction "2_2") (pintype "passive"))
      (node (ref "BM-VR2") (pin "1") (pinfunction "1_1") (pintype "passive"))
      (node (ref "BM-VR4") (pin "3") (pinfunction "3_3") (pintype "passive"))
    )
    (net (code "25") (name "Net-(BM-C110-PadP)") (class "Default")
      (node (ref "BM-C110") (pin "P") (pinfunction "P_P") (pintype "passive"))
      (node (ref "BM-C111") (pin "P") (pinfunction "P_P") (pintype "passive"))
      (node (ref "BM-R116") (pin "1") (pinfunction "1_1") (pintype "passive"))
    )
    (net (code "26") (name "Net-(BM-C111-PadN)") (class "Default")
      (node (ref "BM-C111") (pin "N") (pinfunction "N_N") (pintype "passive"))
      (node (ref "BM-R143") (pin "2") (pinfunction "2_2") (pintype "passive"))
      (node (ref "BM-VR2") (pin "2") (pinfunction "2_2") (pintype "passive"))
      (node (ref "BM-VR2") (pin "3") (pinfunction "3_3") (pintype "passive"))
      (node (ref "BM-VR3") (pin "1") (pinfunction "1_1") (pintype "passive"))
    )
    (net (code "27") (name "Net-(BM-C128-Pad2)") (class "Default")
      (node (ref "BM-C128") (pin "2") (pinfunction "2_2") (pintype "passive"))
      (node (ref "BM-R107") (pin "2") (pinfunction "2_2") (pintype "passive"))
      (node (ref "BM-VR4") (pin "1") (pinfunction "1_1") (pintype "passive"))
    )
    (net (code "28") (name "Net-(BM-RS1-Pad1)") (class "Default")
      (node (ref "BM-RS1") (pin "1") (pinfunction "1_1") (pintype "passive"))
      (node (ref "BM-RS2") (pin "2") (pinfunction "2_2") (pintype "passive"))
    )
    (net (code "29") (name "Net-(C101-Pad1)") (class "Default")
      (node (ref "C101") (pin "1") (pinfunction "1_1") (pintype "passive"))
      (node (ref "IN") (pin "1") (pinfunction "1_1") (pintype "passive"))
    )
    (net (code "30") (name "Net-(C102-Pad2)") (class "Default")
      (node (ref "C102") (pin "2") (pinfunction "2_2") (pintype "passive"))
      (node (ref "R107") (pin "1") (pinfunction "1_1") (pintype "passive"))
    )
    (net (code "31") (name "Net-(C103-Pad1)") (class "Default")
      (node (ref "C103") (pin "1") (pinfunction "1_1") (pintype "passive"))
      (node (ref "C129") (pin "2") (pinfunction "2_2") (pintype "passive"))
      (node (ref "J8") (pin "4") (pinfunction "4_4") (pintype "passive"))
      (node (ref "S1") (pin "0") (pinfunction "0_0") (pintype "passive"))
    )
    (net (code "32") (name "Net-(C104-Pad1)") (class "Default")
      (node (ref "C104") (pin "1") (pinfunction "1_1") (pintype "passive"))
      (node (ref "R111") (pin "1") (pinfunction "1_1") (pintype "passive"))
    )
    (net (code "33") (name "Net-(C106-Pad2)") (class "Default")
      (node (ref "C106") (pin "2") (pinfunction "2_2") (pintype "passive"))
      (node (ref "R111") (pin "2") (pinfunction "2_2") (pintype "passive"))
      (node (ref "R112") (pin "2") (pinfunction "2_2") (pintype "passive"))
    )
    (net (code "34") (name "Net-(C107-PadN)") (class "Default")
      (node (ref "C107") (pin "N") (pinfunction "N_N") (pintype "passive"))
      (node (ref "VR12") (pin "1") (pinfunction "1_1") (pintype "passive"))
    )
    (net (code "35") (name "Net-(C109-PadN)") (class "Default")
      (node (ref "C109") (pin "N") (pinfunction "N_N") (pintype "passive"))
      (node (ref "R117") (pin "2") (pinfunction "2_2") (pintype "passive"))
      (node (ref "R118") (pin "2") (pinfunction "2_2") (pintype "passive"))
    )
    (net (code "36") (name "Net-(C109-PadP)") (class "Default")
      (node (ref "C109") (pin "P") (pinfunction "P_P") (pintype "passive"))
      (node (ref "VR12") (pin "2") (pinfunction "2_2") (pintype "passive"))
    )
    (net (code "37") (name "Net-(C110-PadN)") (class "Default")
      (node (ref "C110") (pin "N") (pinfunction "N_N") (pintype "passive"))
      (node (ref "J8") (pin "3") (pinfunction "3_3") (pintype "passive"))
      (node (ref "RS2") (pin "1") (pinfunction "1_1") (pintype "passive"))
      (node (ref "VR2") (pin "1") (pinfunction "1_1") (pintype "passive"))
      (node (ref "VR4") (pin "1") (pinfunction "1_1") (pintype "passive"))
    )
    (net (code "38") (name "Net-(C110-PadP)") (class "Default")
      (node (ref "C110") (pin "P") (pinfunction "P_P") (pintype "passive"))
      (node (ref "C111") (pin "P") (pinfunction "P_P") (pintype "passive"))
      (node (ref "R116") (pin "1") (pinfunction "1_1") (pintype "passive"))
    )
    (net (code "39") (name "Net-(C111-PadN)") (class "Default")
      (node (ref "C111") (pin "N") (pinfunction "N_N") (pintype "passive"))
      (node (ref "J8") (pin "7") (pinfunction "7_7") (pintype "passive"))
      (node (ref "R134") (pin "2") (pinfunction "2_2") (pintype "passive"))
      (node (ref "S1") (pin "2") (pinfunction "2_2") (pintype "passive"))
      (node (ref "VR2") (pin "2") (pinfunction "2_2") (pintype "passive"))
      (node (ref "VR2") (pin "3") (pinfunction "3_3") (pintype "passive"))
      (node (ref "VR3") (pin "1") (pinfunction "1_1") (pintype "passive"))
    )
    (net (code "40") (name "Net-(C112-Pad1)") (class "Default")
      (node (ref "C112") (pin "1") (pinfunction "1_1") (pintype "passive"))
      (node (ref "R119") (pin "2") (pinfunction "2_2") (pintype "passive"))
      (node (ref "R124") (pin "2") (pinfunction "2_2") (pintype "passive"))
    )
    (net (code "41") (name "Net-(C114-PadN)") (class "Default")
      (node (ref "C114") (pin "N") (pinfunction "N_N") (pintype "passive"))
      (node (ref "R130") (pin "2") (pinfunction "2_2") (pintype "passive"))
      (node (ref "R135") (pin "2") (pinfunction "2_2") (pintype "passive"))
      (node (ref "R136") (pin "2") (pinfunction "2_2") (pintype "passive"))
    )
    (net (code "42") (name "Net-(C115-Pad1)") (class "Default")
      (node (ref "C115") (pin "1") (pinfunction "1_1") (pintype "passive"))
      (node (ref "R135") (pin "1") (pinfunction "1_1") (pintype "passive"))
      (node (ref "TRD102") (pin "1") (pinfunction "1_1") (pintype "passive"))
      (node (ref "VR1") (pin "1") (pinfunction "1_1") (pintype "passive"))
    )
    (net (code "43") (name "Net-(C116-PadN)") (class "Default")
      (node (ref "C116") (pin "N") (pinfunction "N_N") (pintype "passive"))
      (node (ref "LT1") (pin "1") (pinfunction "1_1") (pintype "passive"))
      (node (ref "R133") (pin "2") (pinfunction "2_2") (pintype "passive"))
    )
    (net (code "44") (name "Net-(C117-Pad1)") (class "Default")
      (node (ref "C117") (pin "1") (pinfunction "1_1") (pintype "passive"))
      (node (ref "R136") (pin "1") (pinfunction "1_1") (pintype "passive"))
      (node (ref "TRD101") (pin "1") (pinfunction "1_1") (pintype "passive"))
      (node (ref "VR1") (pin "1") (pinfunction "1_1") (pintype "passive"))
    )
    (net (code "45") (name "Net-(C118-PadN)") (class "Default")
      (node (ref "C118") (pin "N") (pinfunction "N_N") (pintype "passive"))
      (node (ref "LT2") (pin "1") (pinfunction "1_1") (pintype "passive"))
      (node (ref "R140") (pin "2") (pinfunction "2_2") (pintype "passive"))
    )
    (net (code "46") (name "Net-(C119-Pad1)") (class "Default")
      (node (ref "C119") (pin "1") (pinfunction "1_1") (pintype "passive"))
      (node (ref "VR1") (pin "0") (pinfunction "0_0") (pintype "passive"))
    )
    (net (code "47") (name "Net-(C120-Pad1)") (class "Default")
      (node (ref "C120") (pin "1") (pinfunction "1_1") (pintype "passive"))
      (node (ref "VR1") (pin "0") (pinfunction "0_0") (pintype "passive"))
    )
    (net (code "48") (name "Net-(C121-PadN)") (class "Default")
      (node (ref "C121") (pin "N") (pinfunction "N_N") (pintype "passive"))
      (node (ref "R144") (pin "2") (pinfunction "2_2") (pintype "passive"))
      (node (ref "R150") (pin "2") (pinfunction "2_2") (pintype "passive"))
    )
    (net (code "49") (name "Net-(C122-PadN)") (class "Default")
      (node (ref "C122") (pin "N") (pinfunction "N_N") (pintype "passive"))
      (node (ref "R148") (pin "2") (pinfunction "2_2") (pintype "passive"))
      (node (ref "R149") (pin "2") (pinfunction "2_2") (pintype "passive"))
    )
    (net (code "50") (name "Net-(C123-PadN)") (class "Default")
      (node (ref "C123") (pin "N") (pinfunction "N_N") (pintype "passive"))
      (node (ref "VR8") (pin "3") (pinfunction "3_3") (pintype "passive"))
    )
    (net (code "51") (name "Net-(C124-Pad1)") (class "Default")
      (node (ref "C124") (pin "1") (pinfunction "1_1") (pintype "passive"))
      (node (ref "D101") (pin "A") (pinfunction "A_A") (pintype "passive"))
      (node (ref "R158") (pin "1") (pinfunction "1_1") (pintype "passive"))
    )
    (net (code "52") (name "Net-(C125-PadN)") (class "Default")
      (node (ref "C125") (pin "N") (pinfunction "N_N") (pintype "passive"))
      (node (ref "VR10") (pin "3") (pinfunction "3_3") (pintype "passive"))
    )
    (net (code "53") (name "Net-(C128-Pad2)") (class "Default")
      (node (ref "C128") (pin "2") (pinfunction "2_2") (pintype "passive"))
      (node (ref "J7") (pin "1") (pinfunction "1_1") (pintype "passive"))
      (node (ref "R107") (pin "2") (pinfunction "2_2") (pintype "passive"))
      (node (ref "S1") (pin "2") (pinfunction "2_2") (pintype "passive"))
      (node (ref "VR4") (pin "3") (pinfunction "3_3") (pintype "passive"))
    )
    (net (code "54") (name "Net-(C201-PadP)") (class "Default")
      (node (ref "C201") (pin "P") (pinfunction "P_P") (pintype "passive"))
      (node (ref "R206") (pin "2") (pinfunction "2_2") (pintype "passive"))
      (node (ref "TR201") (pin "1") (pinfunction "1_1") (pintype "passive"))
    )
    (net (code "55") (name "Net-(D1-A)") (class "Default")
      (node (ref "D1") (pin "1") (pinfunction "A_1") (pintype "passive"))
      (node (ref "R202") (pin "2") (pinfunction "2_2") (pintype "passive"))
    )
    (net (code "56") (name "Net-(D101-PadC)") (class "Default")
      (node (ref "D101") (pin "C") (pinfunction "C_C") (pintype "passive"))
      (node (ref "D102") (pin "C") (pinfunction "C_C") (pintype "passive"))
    )
    (net (code "57") (name "Net-(FET1-D)") (class "Default")
      (node (ref "C102") (pin "1") (pinfunction "1_1") (pintype "passive"))
      (node (ref "FET1") (pin "3") (pinfunction "D_3") (pintype "passive"))
      (node (ref "R104") (pin "1") (pinfunction "1_1") (pintype "passive"))
      (node (ref "R116") (pin "2") (pinfunction "2_2") (pintype "passive"))
    )
    (net (code "58") (name "Net-(FET1-G)") (class "Default")
      (node (ref "C101") (pin "2") (pinfunction "2_2") (pintype "passive"))
      (node (ref "FET1") (pin "2") (pinfunction "G_2") (pintype "passive"))
      (node (ref "R102") (pin "2") (pinfunction "2_2") (pintype "passive"))
    )
    (net (code "59") (name "Net-(FET1-S)") (class "Default")
      (node (ref "FET1") (pin "1") (pinfunction "S_1") (pintype "passive"))
      (node (ref "R103") (pin "2") (pinfunction "2_2") (pintype "passive"))
    )
    (net (code "60") (name "Net-(FET2-D)") (class "Default")
      (node (ref "C104") (pin "2") (pinfunction "2_2") (pintype "passive"))
      (node (ref "FET2") (pin "3") (pinfunction "D_3") (pintype "passive"))
      (node (ref "R110") (pin "2") (pinfunction "2_2") (pintype "passive"))
    )
    (net (code "61") (name "Net-(FET2-G)") (class "Default")
      (node (ref "C103") (pin "2") (pinfunction "2_2") (pintype "passive"))
      (node (ref "C130") (pin "2") (pinfunction "2_2") (pintype "passive"))
      (node (ref "FET2") (pin "2") (pinfunction "G_2") (pintype "passive"))
      (node (ref "R106") (pin "1") (pinfunction "1_1") (pintype "passive"))
    )
    (net (code "62") (name "Net-(FET2-S)") (class "Default")
      (node (ref "C105") (pin "P") (pinfunction "P_P") (pintype "passive"))
      (node (ref "FET2") (pin "1") (pinfunction "S_1") (pintype "passive"))
      (node (ref "R109") (pin "1") (pinfunction "1_1") (pintype "passive"))
    )
    (net (code "63") (name "Net-(FET3-G)") (class "Default")
      (node (ref "C108") (pin "2") (pinfunction "2_2") (pintype "passive"))
      (node (ref "FET3") (pin "2") (pinfunction "G_2") (pintype "passive"))
      (node (ref "R112") (pin "1") (pinfunction "1_1") (pintype "passive"))
      (node (ref "R113") (pin "2") (pinfunction "2_2") (pintype "passive"))
      (node (ref "R114") (pin "1") (pinfunction "1_1") (pintype "passive"))
    )
    (net (code "64") (name "Net-(FET3-S)") (class "Default")
      (node (ref "C106") (pin "1") (pinfunction "1_1") (pintype "passive"))
      (node (ref "C107") (pin "P") (pinfunction "P_P") (pintype "passive"))
      (node (ref "C131") (pin "2") (pinfunction "2_2") (pintype "passive"))
      (node (ref "FET3") (pin "1") (pinfunction "S_1") (pintype "passive"))
      (node (ref "R115") (pin "1") (pinfunction "1_1") (pintype "passive"))
    )
    (net (code "65") (name "Net-(FET4-D)") (class "Default")
      (node (ref "C113") (pin "1") (pinfunction "1_1") (pintype "passive"))
      (node (ref "FET4") (pin "3") (pinfunction "D_3") (pintype "passive"))
      (node (ref "R126") (pin "2") (pinfunction "2_2") (pintype "passive"))
    )
    (net (code "66") (name "Net-(FET4-G)") (class "Default")
      (node (ref "C112") (pin "2") (pinfunction "2_2") (pintype "passive"))
      (node (ref "FET4") (pin "2") (pinfunction "G_2") (pintype "passive"))
      (node (ref "R121") (pin "2") (pinfunction "2_2") (pintype "passive"))
    )
    (net (code "67") (name "Net-(FET4-S)") (class "Default")
      (node (ref "FET4") (pin "1") (pinfunction "S_1") (pintype "passive"))
      (node (ref "R122") (pin "2") (pinfunction "2_2") (pintype "passive"))
    )
    (net (code "68") (name "Net-(FET5-G)") (class "Default")
      (node (ref "C113") (pin "2") (pinfunction "2_2") (pintype "passive"))
      (node (ref "FET5") (pin "2") (pinfunction "G_2") (pintype "passive"))
      (node (ref "R123") (pin "1") (pinfunction "1_1") (pintype "passive"))
      (node (ref "R127") (pin "2") (pinfunction "2_2") (pintype "passive"))
    )
    (net (code "69") (name "Net-(FET5-S)") (class "Default")
      (node (ref "C114") (pin "P") (pinfunction "P_P") (pintype "passive"))
      (node (ref "FET5") (pin "1") (pinfunction "S_1") (pintype "passive"))
      (node (ref "R129") (pin "1") (pinfunction "1_1") (pintype "passive"))
    )
    (net (code "70") (name "Net-(FET6-G)") (class "Default")
      (node (ref "C115") (pin "2") (pinfunction "2_2") (pintype "passive"))
      (node (ref "FET6") (pin "2") (pinfunction "G_2") (pintype "passive"))
      (node (ref "R128") (pin "2") (pinfunction "2_2") (pintype "passive"))
      (node (ref "R131") (pin "1") (pinfunction "1_1") (pintype "passive"))
    )
    (net (code "71") (name "Net-(FET6-S)") (class "Default")
      (node (ref "C116") (pin "P") (pinfunction "P_P") (pintype "passive"))
      (node (ref "FET6") (pin "1") (pinfunction "S_1") (pintype "passive"))
      (node (ref "R132") (pin "1") (pinfunction "1_1") (pintype "passive"))
    )
    (net (code "72") (name "Net-(FET7-G)") (class "Default")
      (node (ref "C117") (pin "2") (pinfunction "2_2") (pintype "passive"))
      (node (ref "FET7") (pin "2") (pinfunction "G_2") (pintype "passive"))
      (node (ref "R137") (pin "2") (pinfunction "2_2") (pintype "passive"))
      (node (ref "R138") (pin "1") (pinfunction "1_1") (pintype "passive"))
    )
    (net (code "73") (name "Net-(FET7-S)") (class "Default")
      (node (ref "C118") (pin "P") (pinfunction "P_P") (pintype "passive"))
      (node (ref "FET7") (pin "1") (pinfunction "S_1") (pintype "passive"))
      (node (ref "R139") (pin "1") (pinfunction "1_1") (pintype "passive"))
    )
    (net (code "74") (name "Net-(FET8-G)") (class "Default")
      (node (ref "C120") (pin "2") (pinfunction "2_2") (pintype "passive"))
      (node (ref "FET8") (pin "2") (pinfunction "G_2") (pintype "passive"))
      (node (ref "R145") (pin "2") (pinfunction "2_2") (pintype "passive"))
      (node (ref "R146") (pin "1") (pinfunction "1_1") (pintype "passive"))
    )
    (net (code "75") (name "Net-(FET8-S)") (class "Default")
      (node (ref "C122") (pin "P") (pinfunction "P_P") (pintype "passive"))
      (node (ref "FET8") (pin "1") (pinfunction "S_1") (pintype "passive"))
      (node (ref "R147") (pin "1") (pinfunction "1_1") (pintype "passive"))
    )
    (net (code "76") (name "Net-(FET9-G)") (class "Default")
      (node (ref "C119") (pin "2") (pinfunction "2_2") (pintype "passive"))
      (node (ref "FET9") (pin "2") (pinfunction "G_2") (pintype "passive"))
      (node (ref "R141") (pin "2") (pinfunction "2_2") (pintype "passive"))
      (node (ref "R142") (pin "1") (pinfunction "1_1") (pintype "passive"))
    )
    (net (code "77") (name "Net-(FET9-S)") (class "Default")
      (node (ref "C121") (pin "P") (pinfunction "P_P") (pintype "passive"))
      (node (ref "FET9") (pin "1") (pinfunction "S_1") (pintype "passive"))
      (node (ref "R143") (pin "1") (pinfunction "1_1") (pintype "passive"))
    )
    (net (code "78") (name "Net-(IC201-GND)") (class "Default")
      (node (ref "D202") (pin "A") (pinfunction "A_A") (pintype "passive"))
      (node (ref "IC201") (pin "2") (pinfunction "GND_2") (pintype "power_in"))
    )
    (net (code "79") (name "Net-(IC201-IN)") (class "Default")
      (node (ref "C202") (pin "2") (pinfunction "2_2") (pintype "passive"))
      (node (ref "IC201") (pin "1") (pinfunction "IN_1") (pintype "power_in"))
      (node (ref "R201") (pin "1") (pinfunction "1_1") (pintype "passive"))
      (node (ref "R202") (pin "1") (pinfunction "1_1") (pintype "passive"))
    )
    (net (code "80") (name "Net-(IC201-OUT)") (class "Default")
      (node (ref "IC201") (pin "3") (pinfunction "OUT_3") (pintype "power_in"))
      (node (ref "R206") (pin "1") (pinfunction "1_1") (pintype "passive"))
      (node (ref "TR201") (pin "3") (pinfunction "3_3") (pintype "passive"))
    )
    (net (code "81") (name "Net-(J1-Pad2)") (class "Default")
      (node (ref "J1") (pin "2") (pinfunction "2_2") (pintype "passive"))
      (node (ref "J1") (pin "3") (pinfunction "3_3") (pintype "passive"))
      (node (ref "R118") (pin "1") (pinfunction "1_1") (pintype "passive"))
    )
    (net (code "82") (name "Net-(J1-Pad3)") (class "Default")
      (node (ref "J1") (pin "3") (pinfunction "3_3") (pintype "passive"))
      (node (ref "J2") (pin "3") (pinfunction "3_3") (pintype "passive"))
    )
    (net (code "83") (name "Net-(J2-Pad2)") (class "Default")
      (node (ref "J2") (pin "2") (pinfunction "2_2") (pintype "passive"))
      (node (ref "J2") (pin "3") (pinfunction "3_3") (pintype "passive"))
      (node (ref "R124") (pin "1") (pinfunction "1_1") (pintype "passive"))
    )
    (net (code "84") (name "Net-(J3-Pad1)") (class "Default")
      (node (ref "J3") (pin "1") (pinfunction "1_1") (pintype "passive"))
      (node (ref "J3") (pin "3") (pinfunction "3_3") (pintype "passive"))
      (node (ref "J4") (pin "1") (pinfunction "1_1") (pintype "passive"))
      (node (ref "J4") (pin "3") (pinfunction "3_3") (pintype "passive"))
    )
    (net (code "85") (name "Net-(J3-Pad2)") (class "Default")
      (node (ref "J3") (pin "2") (pinfunction "2_2") (pintype "passive"))
      (node (ref "J3") (pin "3") (pinfunction "3_3") (pintype "passive"))
      (node (ref "R150") (pin "1") (pinfunction "1_1") (pintype "passive"))
    )
    (net (code "86") (name "Net-(J4-Pad2)") (class "Default")
      (node (ref "J4") (pin "2") (pinfunction "2_2") (pintype "passive"))
      (node (ref "J4") (pin "3") (pinfunction "3_3") (pintype "passive"))
      (node (ref "R149") (pin "1") (pinfunction "1_1") (pintype "passive"))
    )
    (net (code "87") (name "Net-(J5-Pad0)_1") (class "Default")
      (node (ref "J5") (pin "0") (pinfunction "0_0") (pintype "passive"))
      (node (ref "LT2") (pin "0") (pinfunction "0_0") (pintype "passive"))
    )
    (net (code "88") (name "Net-(J5-Pad0)_2") (class "Default")
      (node (ref "J5") (pin "0") (pinfunction "0_0") (pintype "passive"))
      (node (ref "LT2") (pin "1") (pinfunction "1_1") (pintype "passive"))
    )
    (net (code "89") (name "Net-(J6-Pad0)_1") (class "Default")
      (node (ref "J6") (pin "0") (pinfunction "0_0") (pintype "passive"))
      (node (ref "LT1") (pin "1") (pinfunction "1_1") (pintype "passive"))
    )
    (net (code "90") (name "Net-(J6-Pad0)_2") (class "Default")
      (node (ref "J6") (pin "0") (pinfunction "0_0") (pintype "passive"))
      (node (ref "LT1") (pin "0") (pinfunction "0_0") (pintype "passive"))
    )
    (net (code "91") (name "Net-(J7-Pad2)") (class "Default")
      (node (ref "J7") (pin "2") (pinfunction "2_2") (pintype "passive"))
      (node (ref "RS1") (pin "2") (pinfunction "2_2") (pintype "passive"))
      (node (ref "S1") (pin "2") (pinfunction "2_2") (pintype "passive"))
      (node (ref "VR4") (pin "2") (pinfunction "2_2") (pintype "passive"))
    )
    (net (code "92") (name "Net-(J8-Pad1)") (class "Default")
      (node (ref "J8") (pin "1") (pinfunction "1_1") (pintype "passive"))
      (node (ref "J8") (pin "2") (pinfunction "2_2") (pintype "passive"))
      (node (ref "J8") (pin "6") (pinfunction "6_6") (pintype "passive"))
      (node (ref "S1") (pin "2") (pinfunction "2_2") (pintype "passive"))
    )
    (net (code "93") (name "Net-(J8-Pad5)") (class "Default")
      (node (ref "J8") (pin "5") (pinfunction "5_5") (pintype "passive"))
      (node (ref "S1") (pin "1") (pinfunction "1_1") (pintype "passive"))
      (node (ref "VR3") (pin "3") (pinfunction "3_3") (pintype "passive"))
    )
    (net (code "94") (name "Net-(J201-Pad0)") (class "Default")
      (node (ref "J201") (pin "0") (pinfunction "0_0") (pintype "passive"))
      (node (ref "PS1") (pin "0") (pinfunction "0_0") (pintype "passive"))
    )
    (net (code "95") (name "Net-(PS1-Pad1)") (class "Default")
      (node (ref "PS1") (pin "1") (pinfunction "1_1") (pintype "passive"))
      (node (ref "R201") (pin "2") (pinfunction "2_2") (pintype "passive"))
      (node (ref "R203") (pin "2") (pinfunction "2_2") (pintype "passive"))
    )
    (net (code "96") (name "Net-(R105-Pad2)") (class "Default")
      (node (ref "R105") (pin "2") (pinfunction "2_2") (pintype "passive"))
      (node (ref "R106") (pin "2") (pinfunction "2_2") (pintype "passive"))
      (node (ref "R108") (pin "2") (pinfunction "2_2") (pintype "passive"))
    )
    (net (code "97") (name "Net-(R120-Pad1)") (class "Default")
      (node (ref "R120") (pin "1") (pinfunction "1_1") (pintype "passive"))
      (node (ref "R121") (pin "1") (pinfunction "1_1") (pintype "passive"))
      (node (ref "R125") (pin "2") (pinfunction "2_2") (pintype "passive"))
    )
    (net (code "98") (name "Net-(R151-Pad1)") (class "Default")
      (node (ref "R151") (pin "1") (pinfunction "1_1") (pintype "passive"))
      (node (ref "TR102") (pin "2") (pinfunction "2_2") (pintype "passive"))
    )
    (net (code "99") (name "Net-(R152-Pad2)") (class "Default")
      (node (ref "R152") (pin "2") (pinfunction "2_2") (pintype "passive"))
      (node (ref "VR11") (pin "1") (pinfunction "1_1") (pintype "passive"))
    )
    (net (code "100") (name "Net-(R153-Pad1)") (class "Default")
      (node (ref "R153") (pin "1") (pinfunction "1_1") (pintype "passive"))
      (node (ref "TR101") (pin "2") (pinfunction "2_2") (pintype "passive"))
    )
    (net (code "101") (name "Net-(R154-Pad1)") (class "Default")
      (node (ref "R154") (pin "1") (pinfunction "1_1") (pintype "passive"))
      (node (ref "S2") (pin "1") (pinfunction "1_1") (pintype "passive"))
      (node (ref "VR10") (pin "1") (pinfunction "1_1") (pintype "passive"))
      (node (ref "VR10") (pin "2") (pinfunction "2_2") (pintype "passive"))
    )
    (net (code "102") (name "Net-(R155-Pad1)") (class "Default")
      (node (ref "R155") (pin "1") (pinfunction "1_1") (pintype "passive"))
      (node (ref "S2") (pin "1") (pinfunction "1_1") (pintype "passive"))
      (node (ref "VR8") (pin "1") (pinfunction "1_1") (pintype "passive"))
      (node (ref "VR8") (pin "2") (pinfunction "2_2") (pintype "passive"))
    )
    (net (code "103") (name "Net-(R158-Pad2)") (class "Default")
      (node (ref "R158") (pin "2") (pinfunction "2_2") (pintype "passive"))
      (node (ref "VR6") (pin "0") (pinfunction "0_0") (pintype "passive"))
      (node (ref "VR6") (pin "1") (pinfunction "1_1") (pintype "passive"))
    )
    (net (code "104") (name "Net-(R161-Pad1)") (class "Default")
      (node (ref "R161") (pin "1") (pinfunction "1_1") (pintype "passive"))
      (node (ref "VR6") (pin "0") (pinfunction "0_0") (pintype "passive"))
      (node (ref "VR6") (pin "1") (pinfunction "1_1") (pintype "passive"))
    )
    (net (code "105") (name "Net-(R162-Pad2)") (class "Default")
      (node (ref "R162") (pin "2") (pinfunction "2_2") (pintype "passive"))
      (node (ref "VR9") (pin "1") (pinfunction "1_1") (pintype "passive"))
    )
    (net (code "106") (name "Net-(RS1-Pad1)") (class "Default")
      (node (ref "RS1") (pin "1") (pinfunction "1_1") (pintype "passive"))
      (node (ref "RS2") (pin "2") (pinfunction "2_2") (pintype "passive"))
      (node (ref "S1") (pin "2") (pinfunction "2_2") (pintype "passive"))
    )
    (net (code "107") (name "Net-(S2-Pad0)") (class "Default")
      (node (ref "S2") (pin "0") (pinfunction "0_0") (pintype "passive"))
      (node (ref "TR101") (pin "1") (pinfunction "1_1") (pintype "passive"))
      (node (ref "VR11") (pin "2") (pinfunction "2_2") (pintype "passive"))
    )
    (net (code "108") (name "Net-(S2-Pad0)_1") (class "Default")
      (node (ref "S2") (pin "0") (pinfunction "0_0") (pintype "passive"))
      (node (ref "TR102") (pin "1") (pinfunction "1_1") (pintype "passive"))
      (node (ref "VR9") (pin "2") (pinfunction "2_2") (pintype "passive"))
    )
    (net (code "109") (name "Net-(TR101-Pad3)") (class "Default")
      (node (ref "TR101") (pin "3") (pinfunction "3_3") (pintype "passive"))
      (node (ref "TRD102") (pin "2") (pinfunction "2_2") (pintype "passive"))
    )
    (net (code "110") (name "Net-(TR102-Pad3)") (class "Default")
      (node (ref "TR102") (pin "3") (pinfunction "3_3") (pintype "passive"))
      (node (ref "TRD101") (pin "2") (pinfunction "2_2") (pintype "passive"))
    )
    (net (code "111") (name "Net-(TRD101-Pad0)") (class "Default")
      (node (ref "TRD101") (pin "0") (pinfunction "0_0") (pintype "passive"))
      (node (ref "VR5") (pin "1") (pinfunction "1_1") (pintype "passive"))
    )
    (net (code "112") (name "Net-(TRD102-Pad0)") (class "Default")
      (node (ref "TRD102") (pin "0") (pinfunction "0_0") (pintype "passive"))
      (node (ref "VR5") (pin "1") (pinfunction "1_1") (pintype "passive"))
    )
    (net (code "113") (name "Net-(U102A-IN1+)") (class "Default")
      (node (ref "R159") (pin "1") (pinfunction "1_1") (pintype "passive"))
      (node (ref "U102") (pin "3") (pinfunction "IN1+_3") (pintype "input"))
    )
    (net (code "114") (name "Net-(U102A-IN1-)") (class "Default")
      (node (ref "R156") (pin "2") (pinfunction "2_2") (pintype "passive"))
      (node (ref "R157") (pin "1") (pinfunction "1_1") (pintype "passive"))
      (node (ref "U102") (pin "2") (pinfunction "IN1-_2") (pintype "input"))
    )
    (net (code "115") (name "Net-(U102A-OUT1)") (class "Default")
      (node (ref "C125") (pin "P") (pinfunction "P_P") (pintype "passive"))
      (node (ref "R156") (pin "1") (pinfunction "1_1") (pintype "passive"))
      (node (ref "U102") (pin "1") (pinfunction "OUT1_1") (pintype "output"))
    )
    (net (code "116") (name "Net-(U102B-IN2+)") (class "Default")
      (node (ref "C127") (pin "2") (pinfunction "2_2") (pintype "passive"))
      (node (ref "U102") (pin "5") (pinfunction "IN2+_5") (pintype "input"))
      (node (ref "VR6") (pin "0") (pinfunction "0_0") (pintype "passive"))
    )
    (net (code "117") (name "Net-(U102B-IN2-)") (class "Default")
      (node (ref "C126") (pin "1") (pinfunction "1_1") (pintype "passive"))
      (node (ref "R160") (pin "2") (pinfunction "2_2") (pintype "passive"))
      (node (ref "U102") (pin "6") (pinfunction "IN2-_6") (pintype "input"))
      (node (ref "VR7") (pin "3") (pinfunction "3_3") (pintype "passive"))
    )
    (net (code "118") (name "Net-(U102B-OUT2)") (class "Default")
      (node (ref "C123") (pin "P") (pinfunction "P_P") (pintype "passive"))
      (node (ref "C124") (pin "2") (pinfunction "2_2") (pintype "passive"))
      (node (ref "C126") (pin "2") (pinfunction "2_2") (pintype "passive"))
      (node (ref "R157") (pin "2") (pinfunction "2_2") (pintype "passive"))
      (node (ref "R160") (pin "1") (pinfunction "1_1") (pintype "passive"))
      (node (ref "U102") (pin "7") (pinfunction "OUT2_7") (pintype "output"))
    )
    (net (code "119") (name "unconnected-(BH-C103-Pad2)") (class "Default")
      (node (ref "BH-C103") (pin "2") (pinfunction "2_2") (pintype "passive"))
    )
    (net (code "120") (name "unconnected-(BH-VR3-Pad3)") (class "Default")
      (node (ref "BH-VR3") (pin "3") (pinfunction "3_3") (pintype "passive+no_connect"))
    )
    (net (code "121") (name "unconnected-(BL-C103-Pad2)") (class "Default")
      (node (ref "BL-C103") (pin "2") (pinfunction "2_2") (pintype "passive"))
    )
    (net (code "122") (name "unconnected-(BM-C103-Pad2)") (class "Default")
      (node (ref "BM-C103") (pin "2") (pinfunction "2_2") (pintype "passive"))
    )
    (net (code "123") (name "unconnected-(J3-Pad3)") (class "Default")
      (node (ref "J3") (pin "3") (pinfunction "3_3") (pintype "passive"))
    )
    (net (code "124") (name "unconnected-(J4-Pad3)") (class "Default")
      (node (ref "J4") (pin "3") (pinfunction "3_3") (pintype "passive"))
    )
    (net (code "125") (name "unconnected-(J5-Pad0)") (class "Default")
      (node (ref "J5") (pin "0") (pinfunction "0_0") (pintype "passive"))
    )
    (net (code "126") (name "unconnected-(J6-Pad0)") (class "Default")
      (node (ref "J6") (pin "0") (pinfunction "0_0") (pintype "passive"))
    )
    (net (code "127") (name "unconnected-(J8-Pad8)") (class "Default")
      (node (ref "J8") (pin "8") (pinfunction "8_8") (pintype "passive"))
    )
    (net (code "128") (name "unconnected-(S1-Pad2)") (class "Default")
      (node (ref "S1") (pin "2") (pinfunction "2_2") (pintype "passive"))
    )
  )
)
